# RM2025___IMCA.net
KiCad netlist of a schematic drawn in EasyEDA Pro
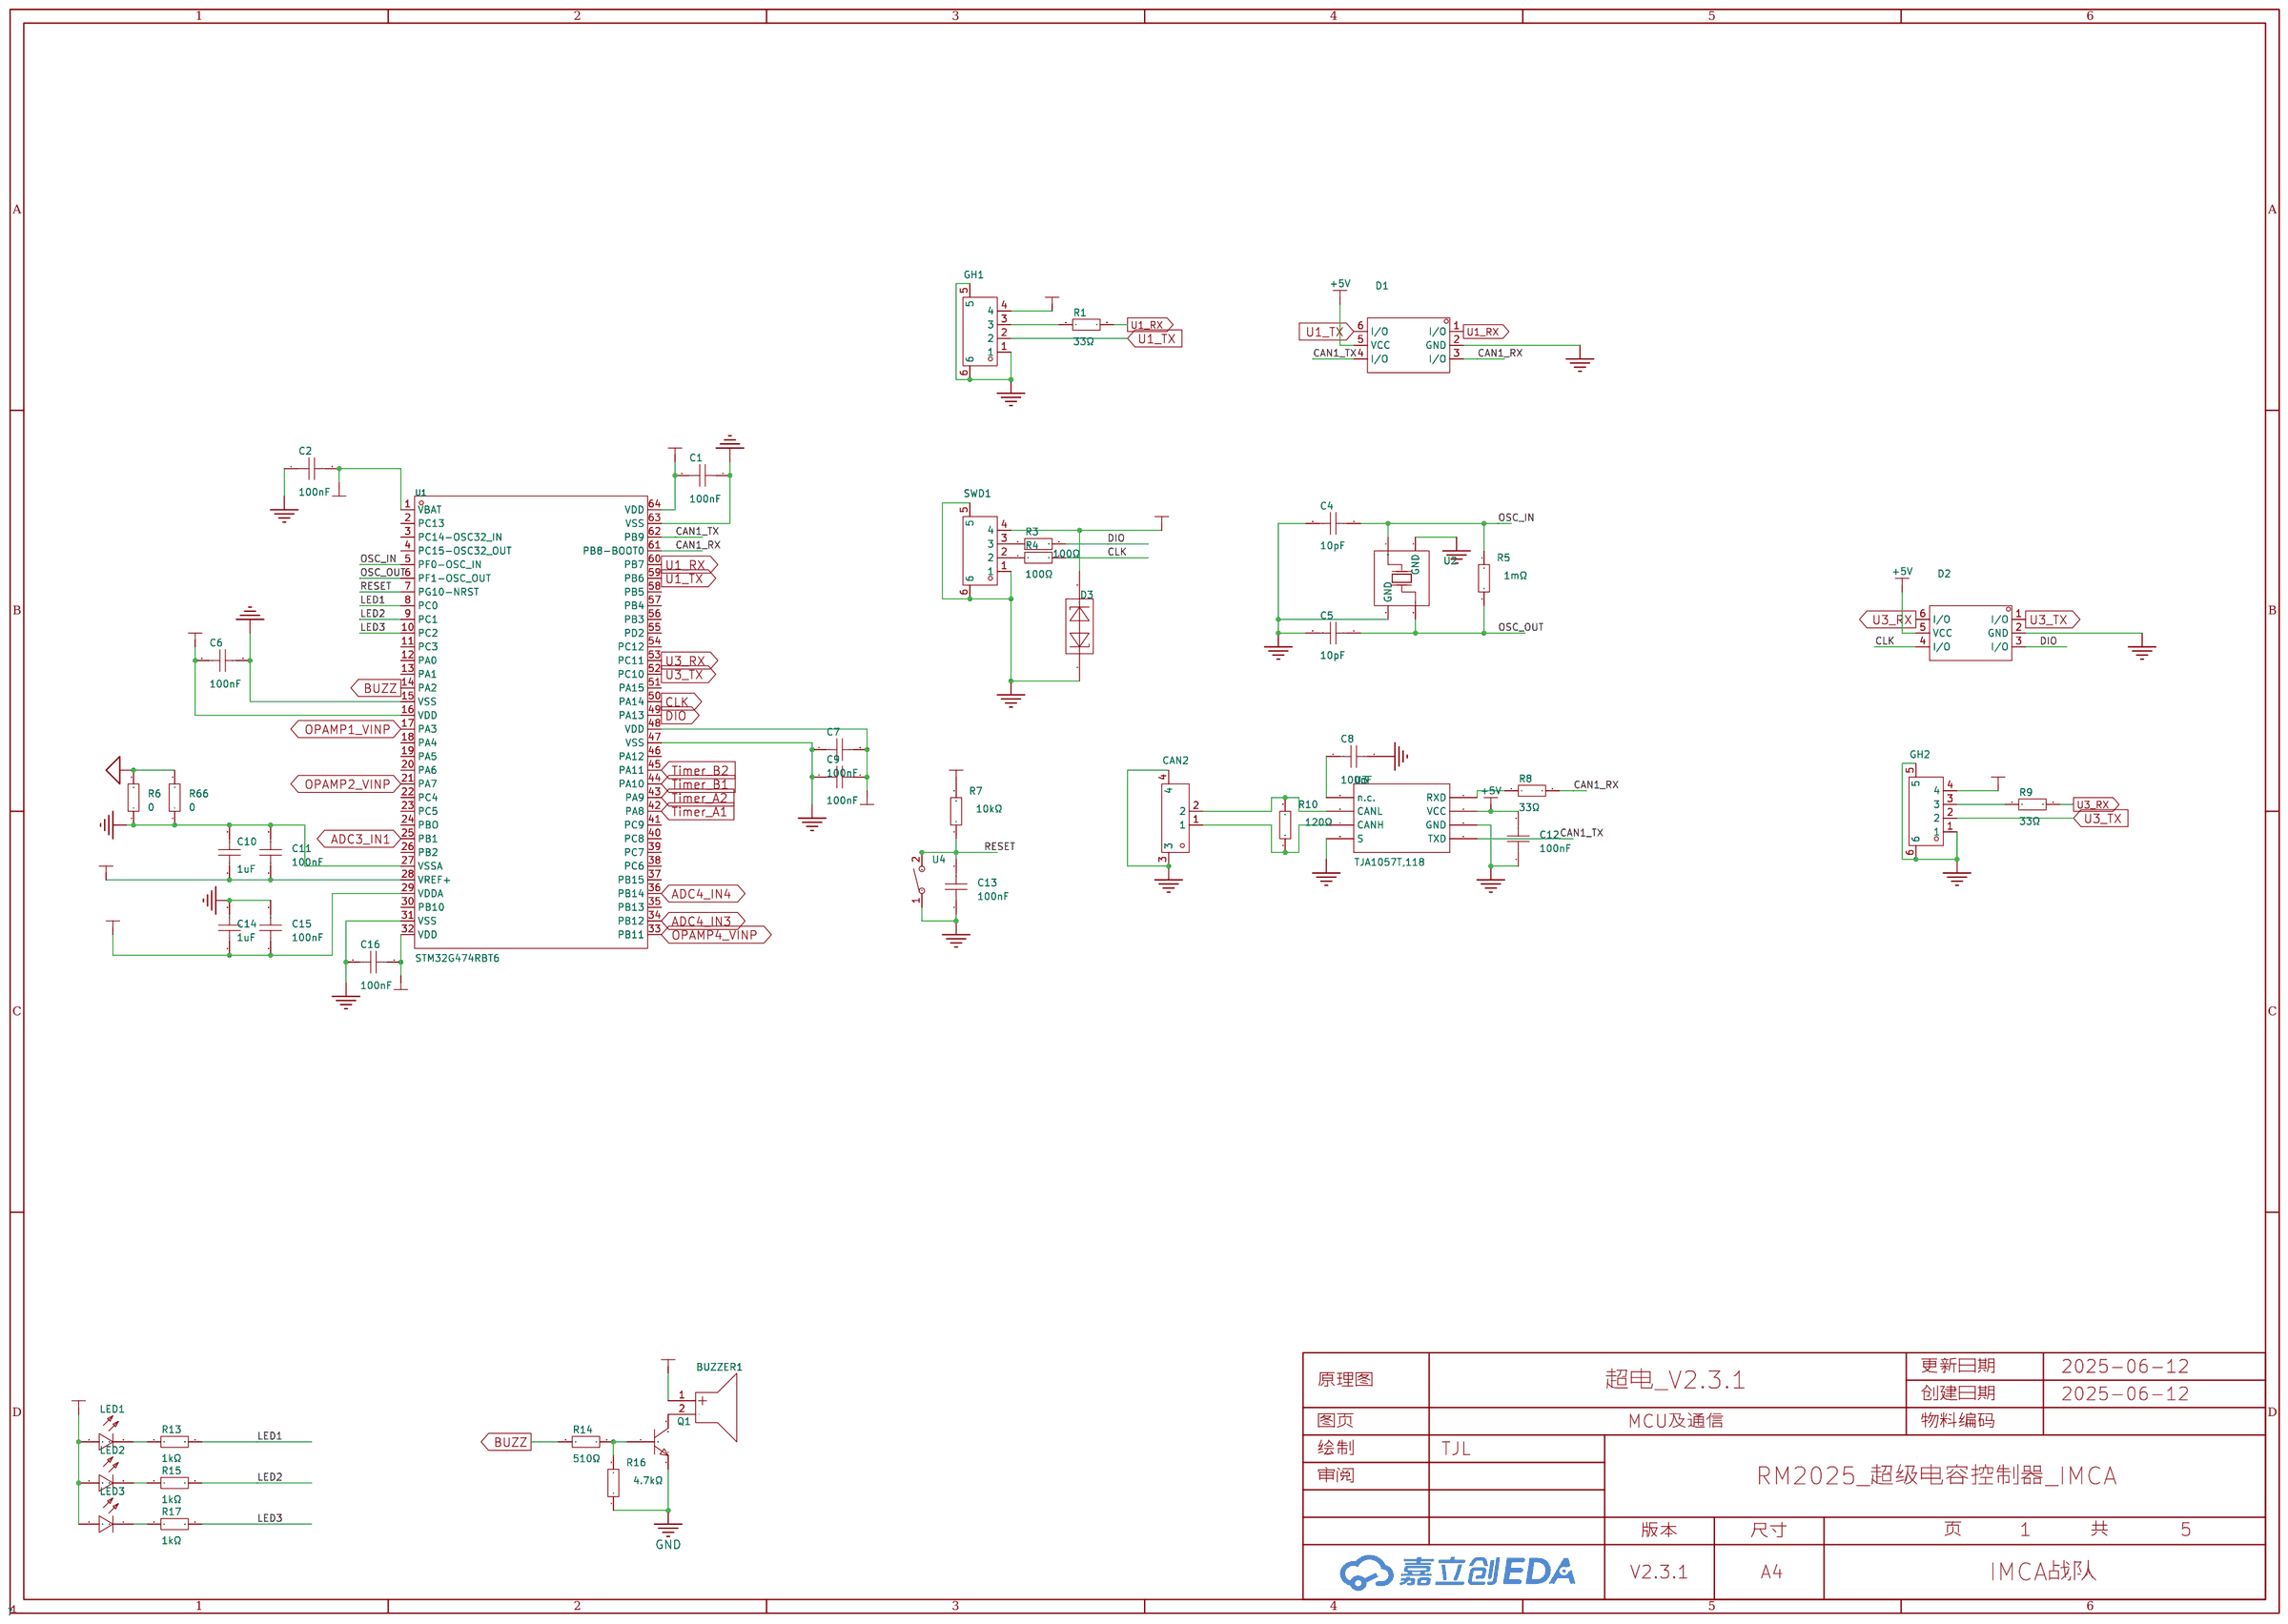
[diagram p0: MCU及通信]
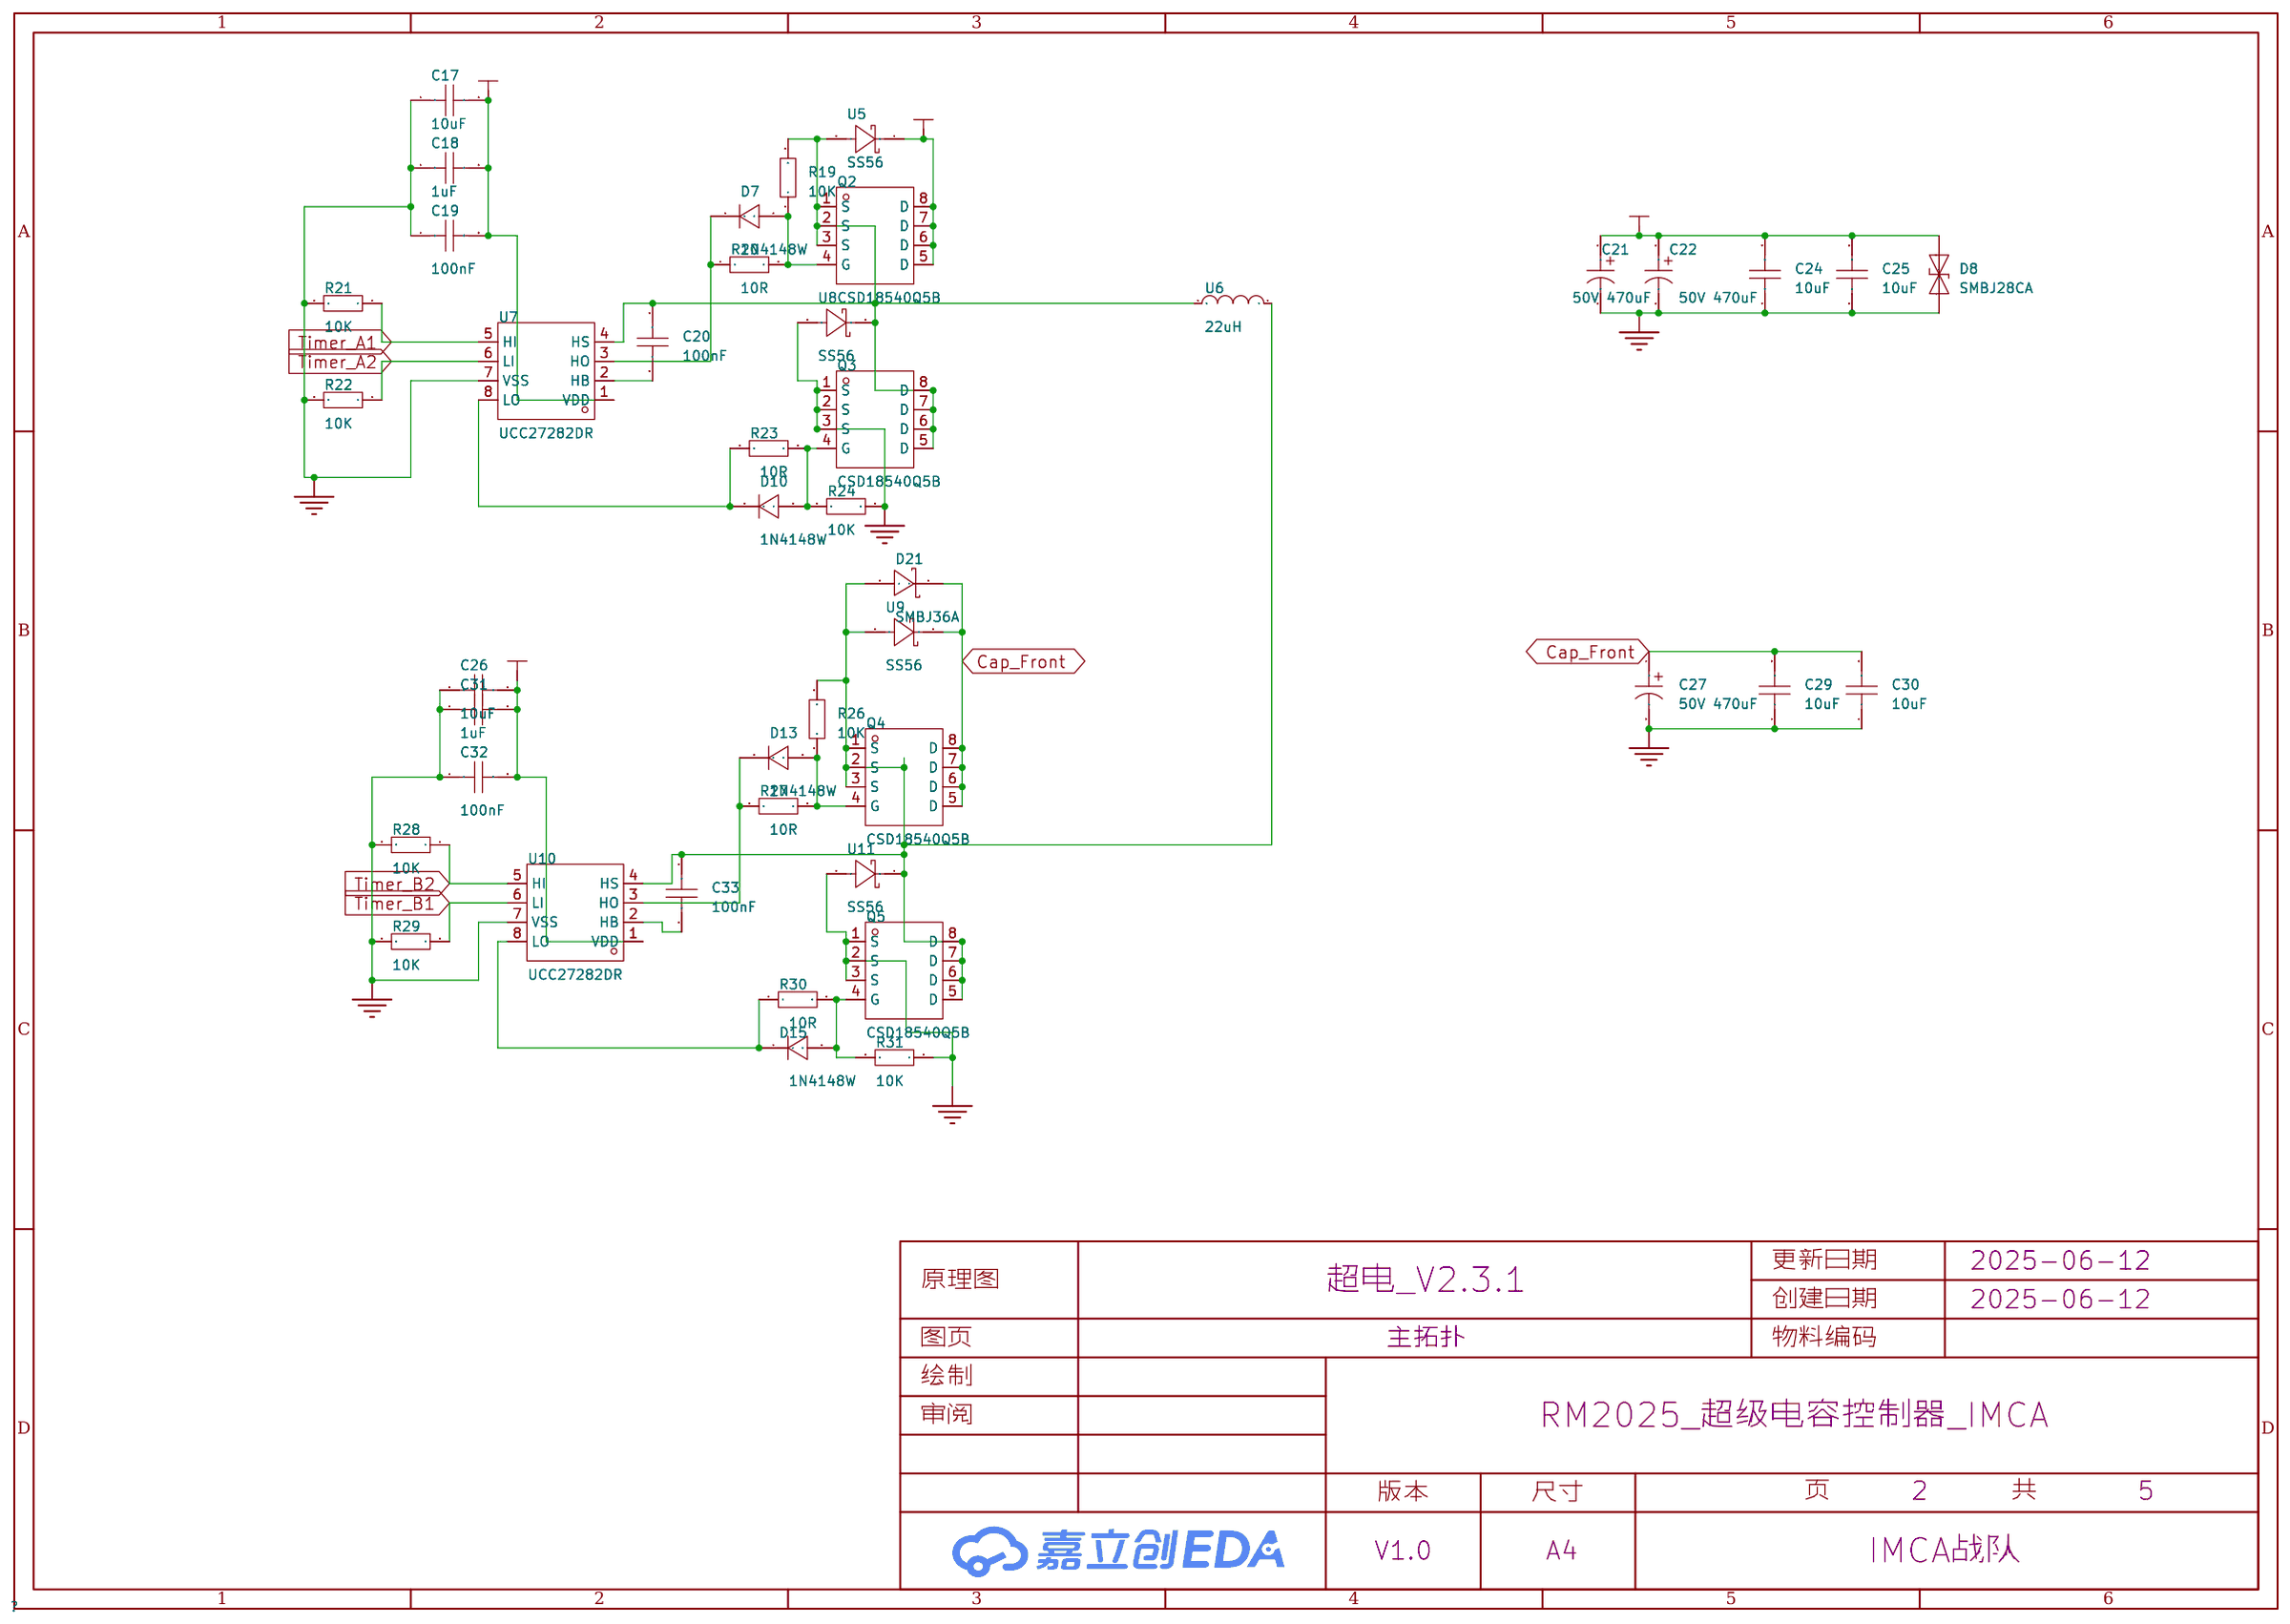
[diagram p1: 主拓扑]
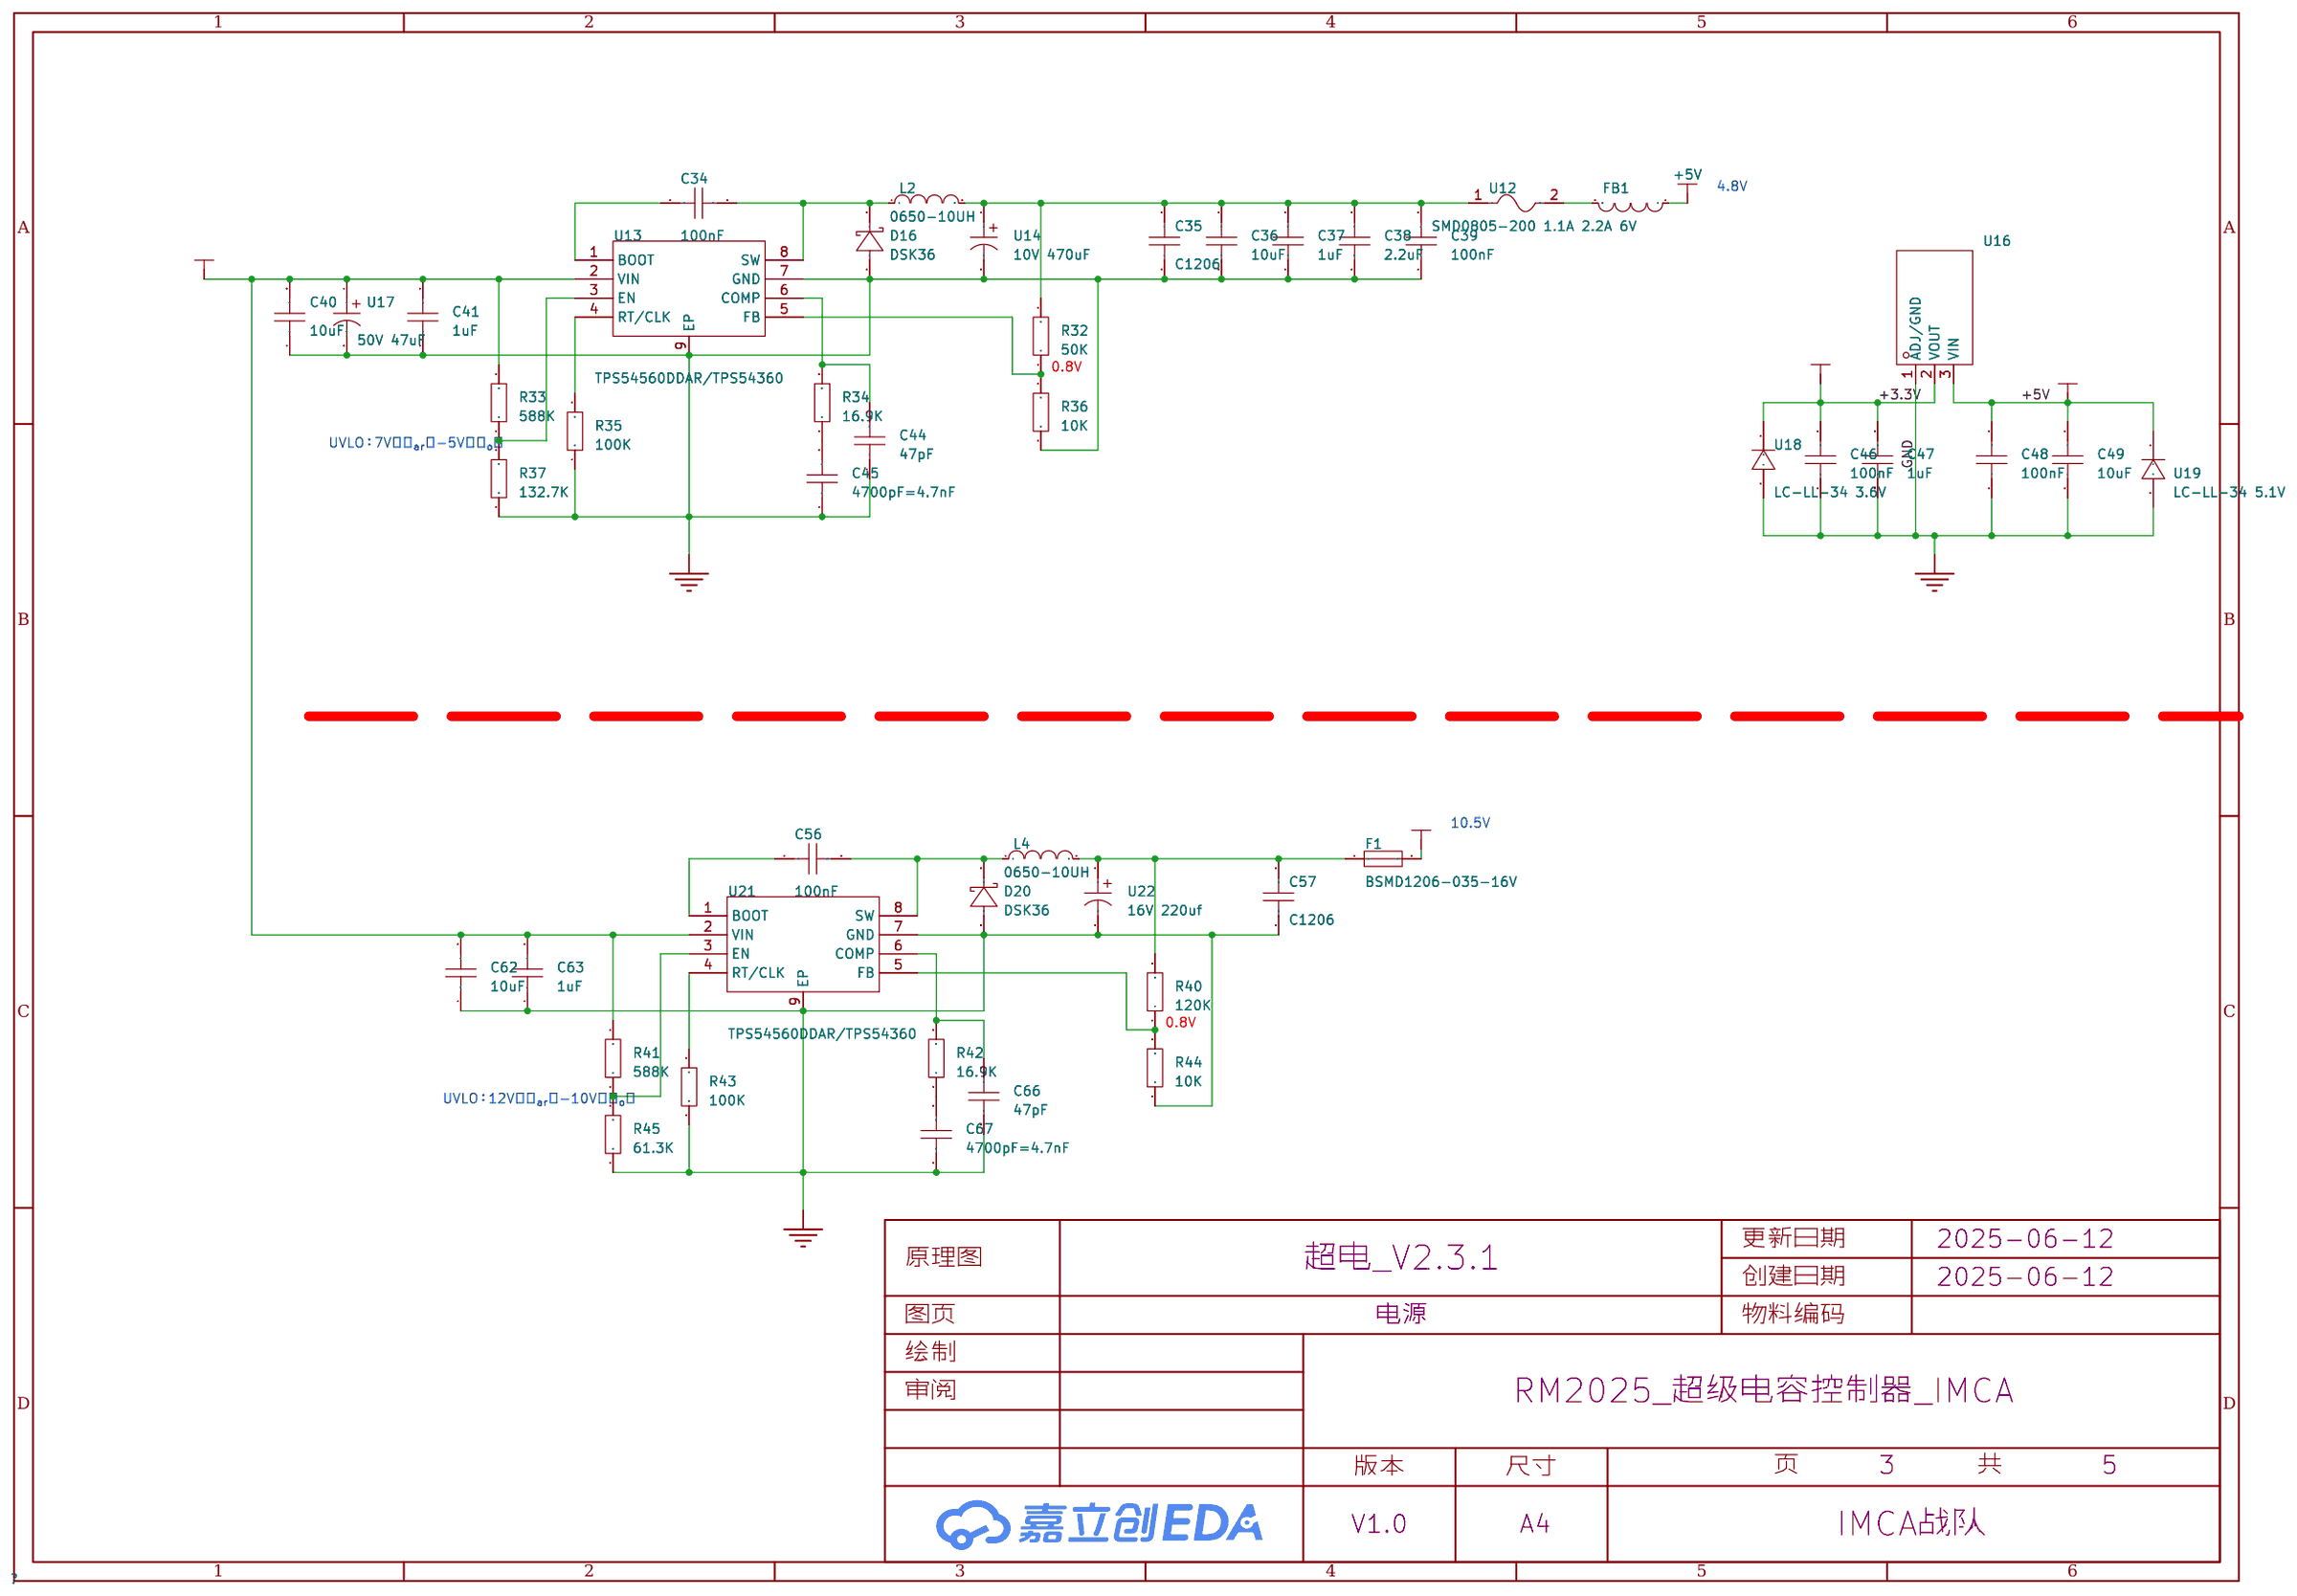
[diagram p2: 电源]
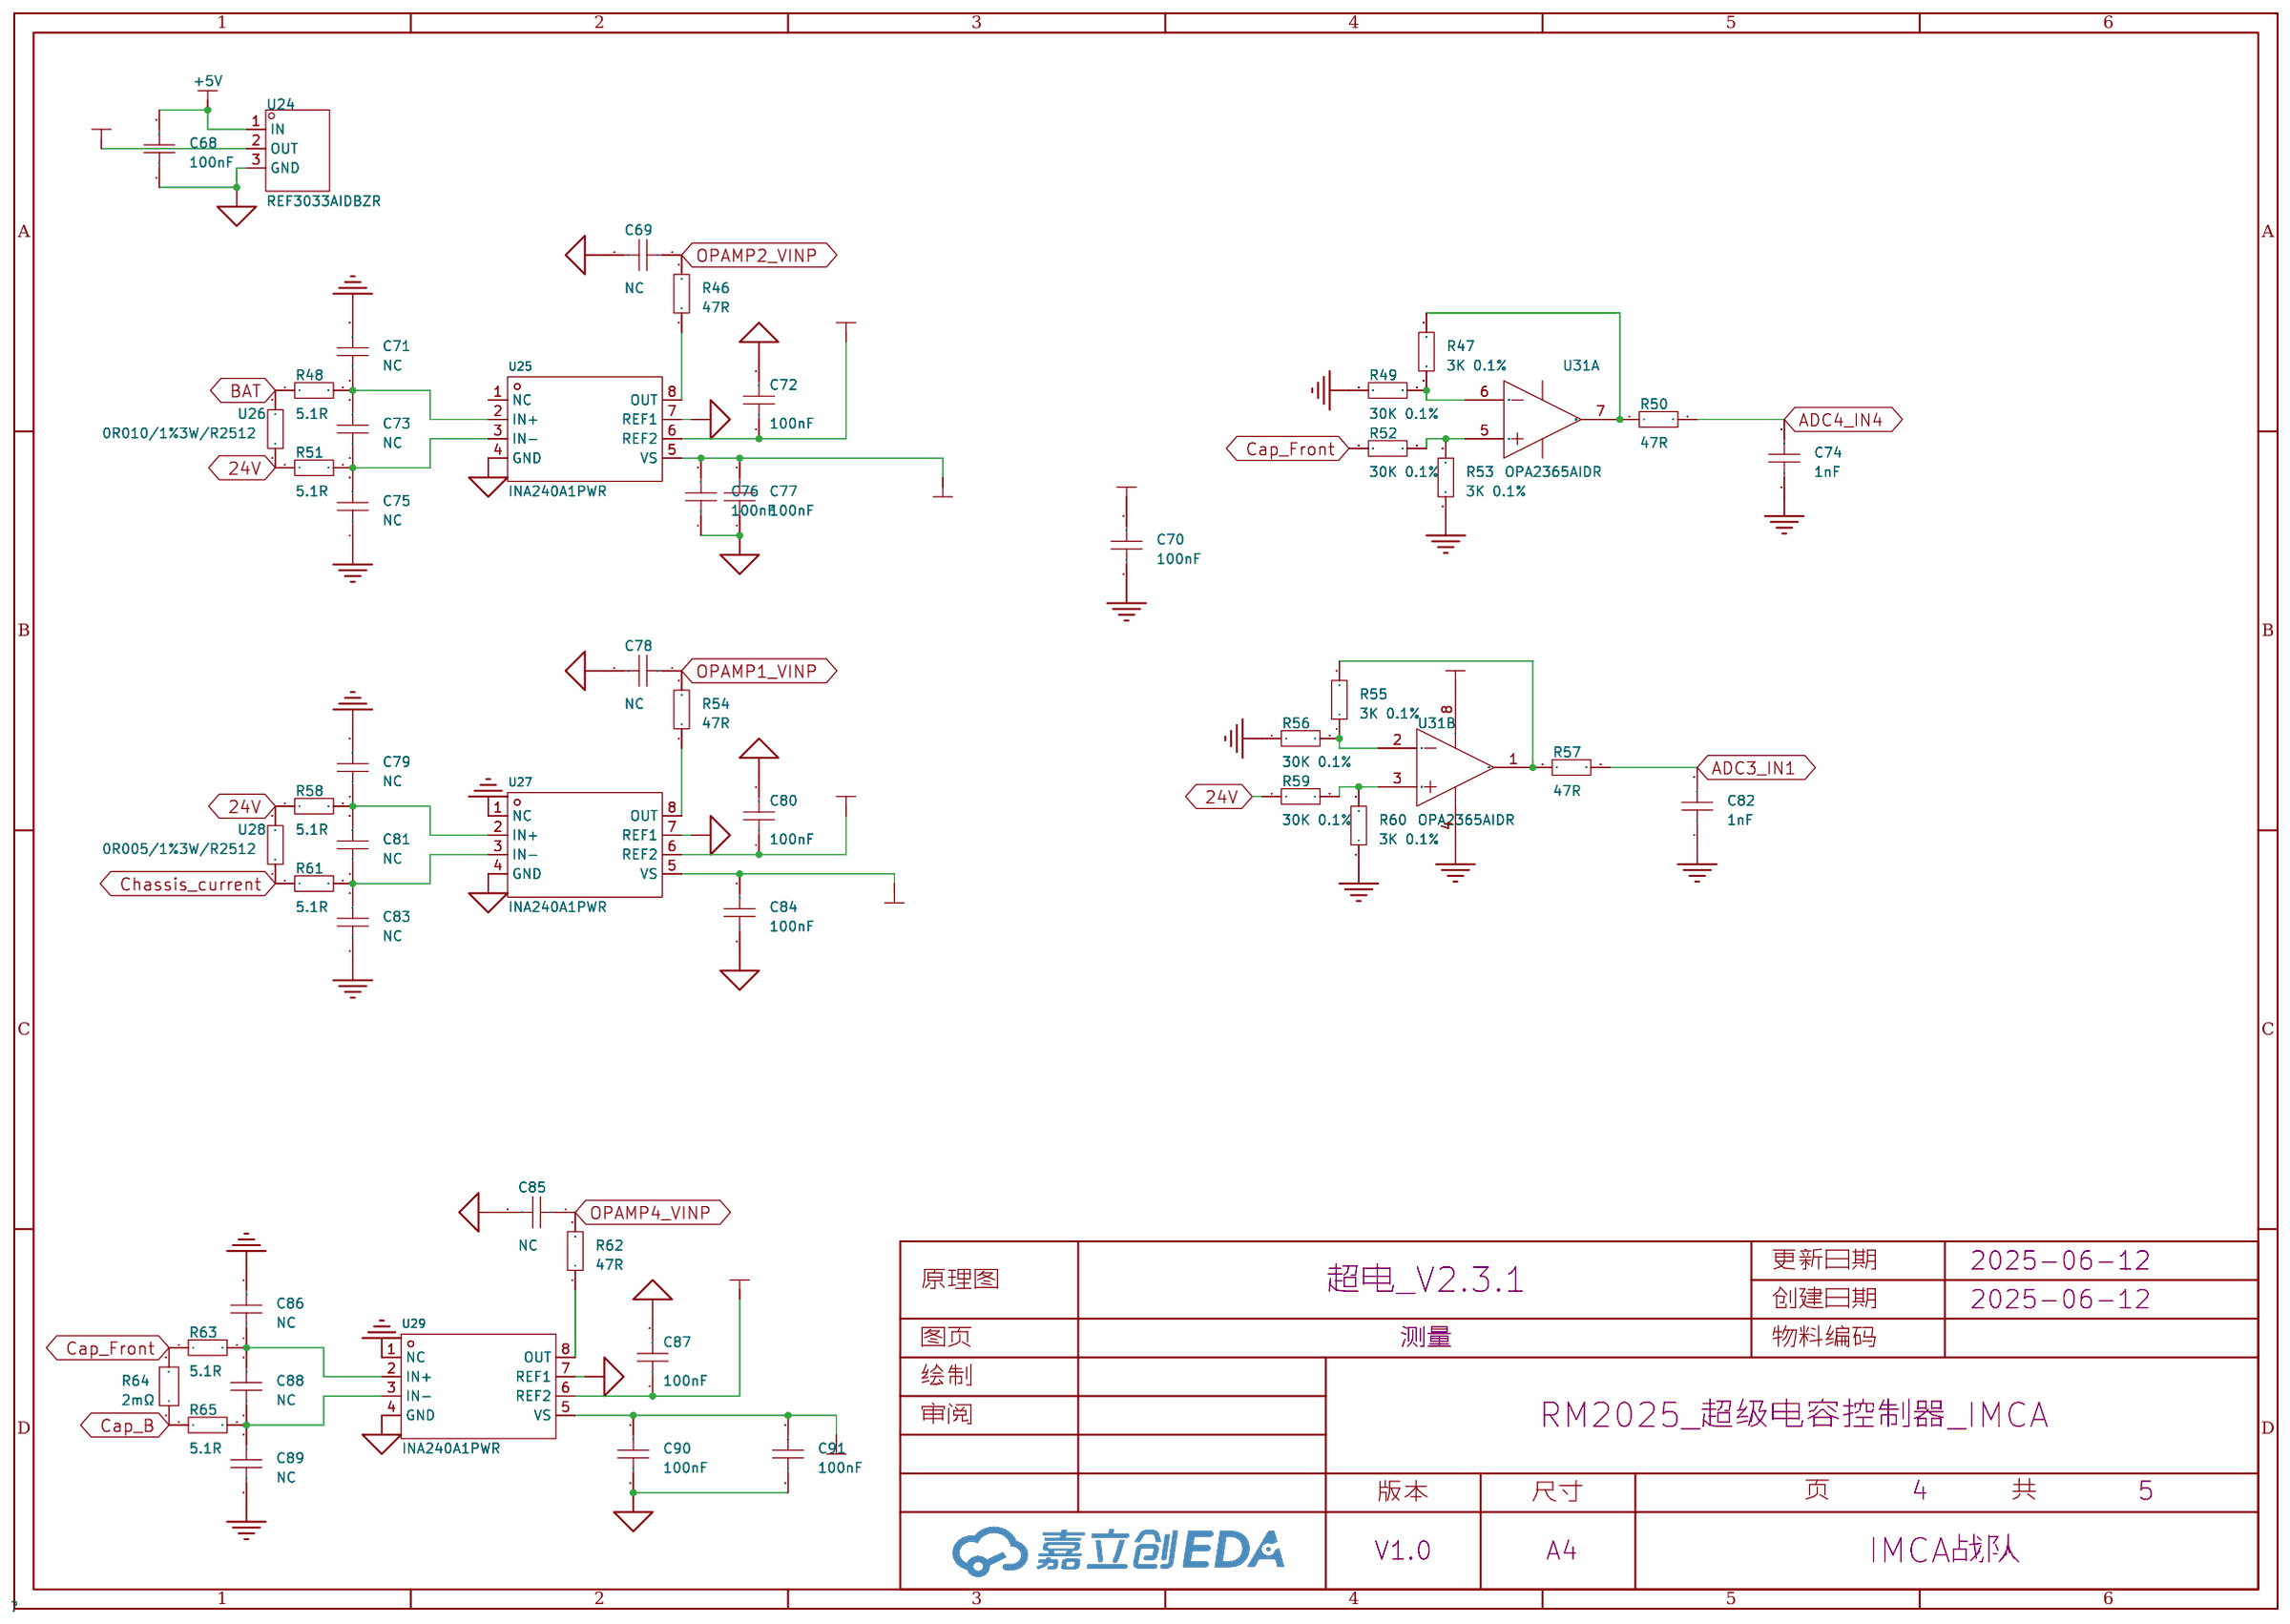
[diagram p3: 测量]
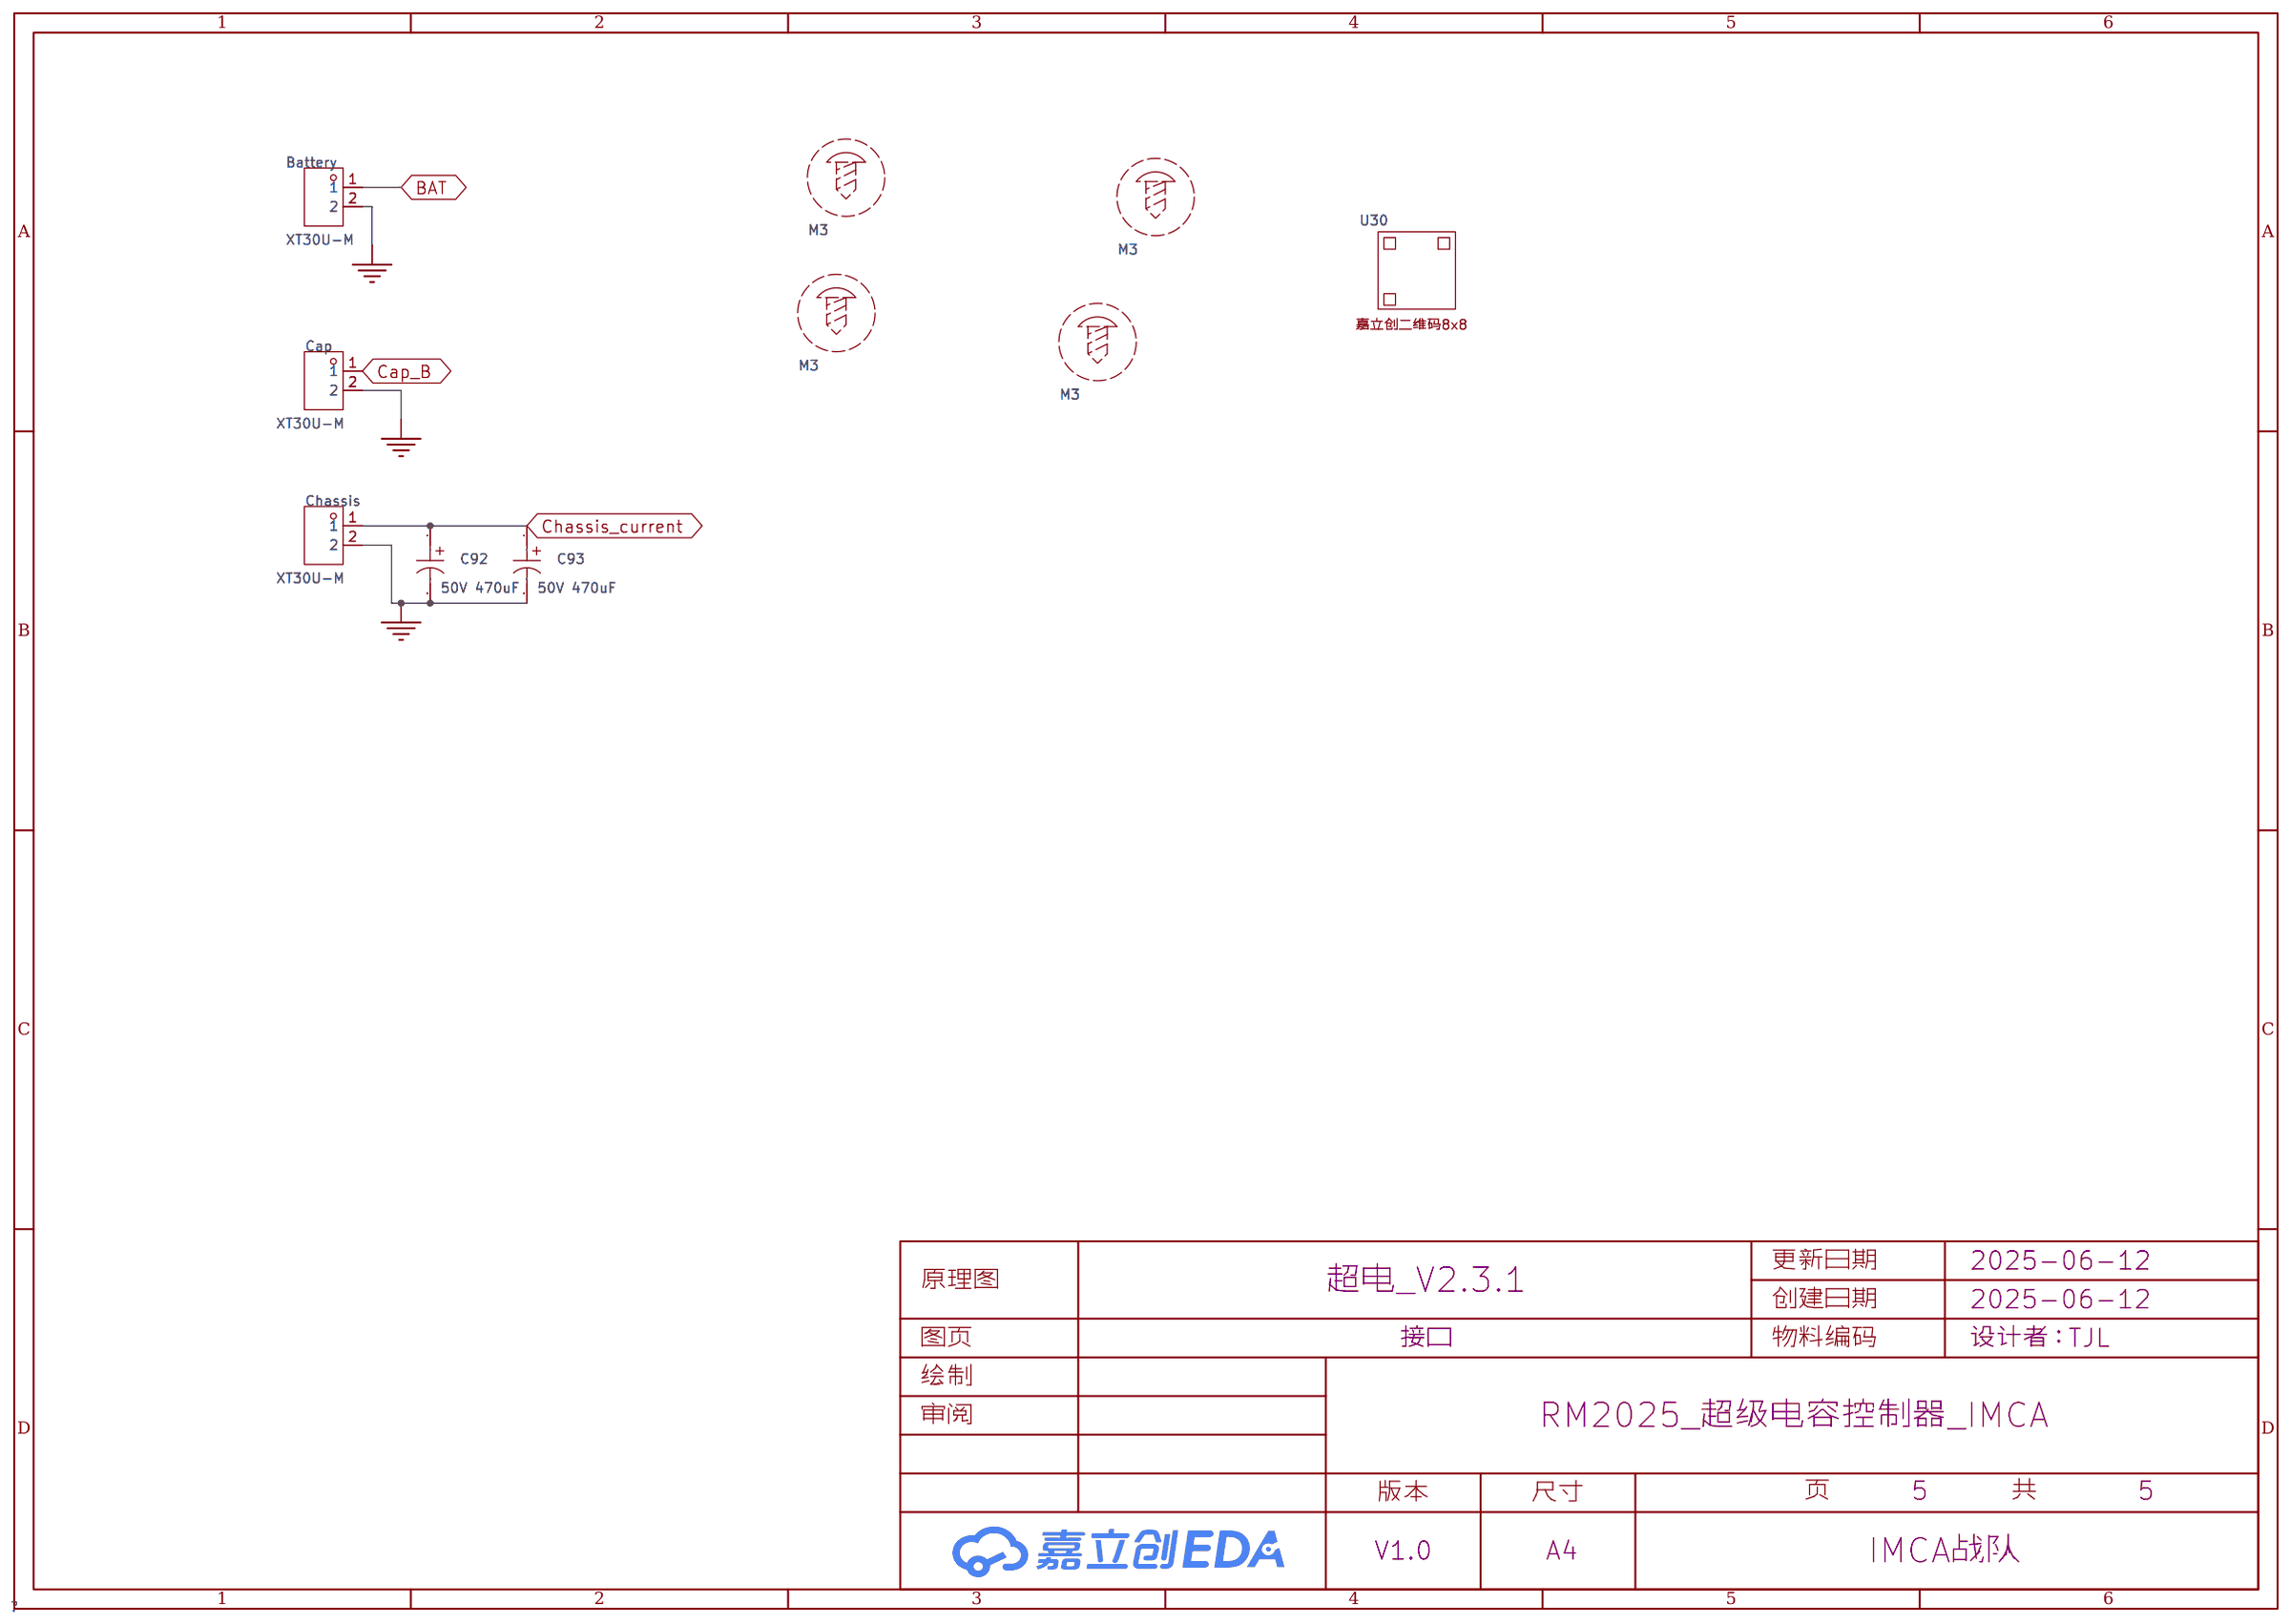
[diagram p4: 接口]

(export (version "E")
  (design (tool "Eeschema 10.0.6"))
  (components
    (comp (ref "BUZZER1")
      (value "~")
      (footprint "easyedapro:BUZ-TH_BD9.0-P5.00-D0.6-L-FD")
      (fields (field (name "Manufacturer Part") "有源蜂鸣器直径9*5.5mm3V"))
      (libsource (lib "easyedapro") (part "有源蜂鸣器直径9*5.5MM3V"))
    )
    (comp (ref "C1")
      (value "100nF")
      (footprint "easyedapro:C1206")
      (libsource (lib "easyedapro") (part "CapAcitance"))
    )
    (comp (ref "C2")
      (value "100nF")
      (footprint "easyedapro:C1206")
      (libsource (lib "easyedapro") (part "CapAcitance"))
    )
    (comp (ref "C4")
      (value "10pF")
      (footprint "easyedapro:C0603")
      (description "容值:100nF;精度:±10%;额定电压:50V;温度系数:X7R;")
      (fields
        (field (name "Manufacturer Part") "CC0603KRX7R9BB104")
        (field (name "Manufacturer") "YAGEO(国巨)")
      )
      (libsource (lib "easyedapro") (part "CC0603KRX7R9BB104"))
    )
    (comp (ref "C5")
      (value "10pF")
      (footprint "easyedapro:C0603")
      (description "容值:100nF;精度:±10%;额定电压:50V;温度系数:X7R;")
      (fields
        (field (name "Manufacturer Part") "CC0603KRX7R9BB104")
        (field (name "Manufacturer") "YAGEO(国巨)")
      )
      (libsource (lib "easyedapro") (part "CC0603KRX7R9BB104"))
    )
    (comp (ref "C6")
      (value "100nF")
      (footprint "easyedapro:C1206")
      (libsource (lib "easyedapro") (part "CapAcitance"))
    )
    (comp (ref "C7")
      (value "100nF")
      (footprint "easyedapro:C1206")
      (libsource (lib "easyedapro") (part "CapAcitance"))
    )
    (comp (ref "C8")
      (value "100nF")
      (footprint "easyedapro:C1206")
      (libsource (lib "easyedapro") (part "CapAcitance"))
    )
    (comp (ref "C9")
      (value "100nF")
      (footprint "easyedapro:C1206")
      (libsource (lib "easyedapro") (part "CapAcitance"))
    )
    (comp (ref "C10")
      (value "1uF")
      (footprint "easyedapro:C1206")
      (libsource (lib "easyedapro") (part "CapAcitance"))
    )
    (comp (ref "C11")
      (value "100nF")
      (footprint "easyedapro:C1206")
      (libsource (lib "easyedapro") (part "CapAcitance"))
    )
    (comp (ref "C12")
      (value "100nF")
      (footprint "easyedapro:C1206")
      (libsource (lib "easyedapro") (part "CapAcitance"))
    )
    (comp (ref "C13")
      (value "100nF")
      (footprint "easyedapro:C1206")
      (libsource (lib "easyedapro") (part "CapAcitance"))
    )
    (comp (ref "C14")
      (value "1uF")
      (footprint "easyedapro:C1206")
      (libsource (lib "easyedapro") (part "CapAcitance"))
    )
    (comp (ref "C15")
      (value "100nF")
      (footprint "easyedapro:C1206")
      (libsource (lib "easyedapro") (part "CapAcitance"))
    )
    (comp (ref "C16")
      (value "100nF")
      (footprint "easyedapro:C1206")
      (libsource (lib "easyedapro") (part "CapAcitance"))
    )
    (comp (ref "CAN2")
      (value "~")
      (footprint "easyedapro:CONN-SMD_2P-P1.25_GH1.25-2P")
      (fields
        (field (name "Manufacturer Part") "GH1.25-2PLTPZ")
        (field (name "Manufacturer") "BOOMELE(博穆精密)")
      )
      (libsource (lib "easyedapro") (part "GH1.25-2PLTPZ"))
    )
    (comp (ref "D1")
      (value "SRV05-4HTG-D")
      (footprint "easyedapro:SOT-23-6_L2.9-W1.6-P0.95-LS2.8-BR")
      (fields
        (field (name "Manufacturer Part") "BST236A054U")
        (field (name "Manufacturer") "Bourne Semicon (Shenzhen)")
      )
      (libsource (lib "easyedapro") (part "BST236A054U"))
    )
    (comp (ref "D2")
      (value "SRV05-4HTG-D")
      (footprint "easyedapro:SOT-23-6_L2.9-W1.6-P0.95-LS2.8-BR")
      (fields
        (field (name "Manufacturer Part") "BST236A054U")
        (field (name "Manufacturer") "Bourne Semicon (Shenzhen)")
      )
      (libsource (lib "easyedapro") (part "BST236A054U"))
    )
    (comp (ref "D3")
      (value "~")
      (footprint "easyedapro:SOD-323_L1.8-W1.3-LS2.5-BI")
      (description "极性:Bidirectional;反向关断电压（典型值）:5V;击穿电压（最小值）:7V;箝位电压:33V;峰值脉冲电流（10/1000us）:15A;")
      (fields
        (field (name "Manufacturer Part") "PESD5V0L1BA,115")
        (field (name "Manufacturer") "Nexperia(安世)")
      )
      (libsource (lib "easyedapro") (part "PESD5V0L1BA,115"))
    )
    (comp (ref "GH1")
      (value "U1")
      (footprint "easyedapro:CONN-SMD_4P-P2.00_GH1.25-WS-4P")
      (fields (field (name "Manufacturer Part") "GH1.25-WS-4P"))
      (libsource (lib "easyedapro") (part "GH1.25-WS-4P"))
    )
    (comp (ref "GH2")
      (value "U3")
      (footprint "easyedapro:CONN-SMD_4P-P2.00_GH1.25-WS-4P")
      (fields (field (name "Manufacturer Part") "GH1.25-WS-4P"))
      (libsource (lib "easyedapro") (part "GH1.25-WS-4P"))
    )
    (comp (ref "LED1")
      (value "~")
      (footprint "easyedapro:LED0603-R-RD")
      (description "照明颜色:翠绿;色温 - CCT（K）:-;主波长/色坐标:520~535nm;")
      (fields
        (field (name "Manufacturer Part") "19-217/GHC-YR1S2/3T")
        (field (name "Manufacturer") "EVERLIGHT(台湾亿光)")
      )
      (libsource (lib "easyedapro") (part "19-217/GHC-YR1S2/3T"))
    )
    (comp (ref "LED2")
      (value "~")
      (footprint "easyedapro:LED0603-R-RD")
      (description "照明颜色:翠绿;色温 - CCT（K）:-;主波长/色坐标:520~535nm;")
      (fields
        (field (name "Manufacturer Part") "19-217/GHC-YR1S2/3T")
        (field (name "Manufacturer") "EVERLIGHT(台湾亿光)")
      )
      (libsource (lib "easyedapro") (part "19-217/GHC-YR1S2/3T"))
    )
    (comp (ref "LED3")
      (value "~")
      (footprint "easyedapro:LED0603-R-RD")
      (description "照明颜色:翠绿;色温 - CCT（K）:-;主波长/色坐标:520~535nm;")
      (fields
        (field (name "Manufacturer Part") "19-217/GHC-YR1S2/3T")
        (field (name "Manufacturer") "EVERLIGHT(台湾亿光)")
      )
      (libsource (lib "easyedapro") (part "19-217/GHC-YR1S2/3T"))
    )
    (comp (ref "Q1")
      (value "~")
      (footprint "easyedapro:SOT-23-3_L2.9-W1.3-P1.90-LS2.4-BR")
      (description "额定功率:300mW;集电极电流Ic:1.5A;集射极击穿电压Vce:25V;晶体管类型:NPN;")
      (fields (field (name "Manufacturer Part") "SS8050"))
      (libsource (lib "easyedapro") (part "SS8050_C139513"))
    )
    (comp (ref "R1")
      (value "33Ω")
      (footprint "easyedapro:R0603")
      (description "电阻类型:薄膜电阻;阻值:10kΩ;精度:±0.1%;功率:100mW;温度系数:±25ppm/;最大工作电压:75V;工作温度范围:-55~+155;")
      (fields
        (field (name "Manufacturer Part") "TR0603B10K0P0525Z")
        (field (name "Manufacturer") "EVER OHMS(天二科技)")
      )
      (libsource (lib "easyedapro") (part "TR0603B10KP05250.1W"))
    )
    (comp (ref "R3")
      (value "100Ω")
      (footprint "easyedapro:R0603")
      (description "电阻类型:薄膜电阻;阻值:10kΩ;精度:±0.1%;功率:100mW;温度系数:±25ppm/;最大工作电压:75V;工作温度范围:-55~+155;")
      (fields
        (field (name "Manufacturer Part") "TR0603B10K0P0525Z")
        (field (name "Manufacturer") "EVER OHMS(天二科技)")
      )
      (libsource (lib "easyedapro") (part "TR0603B10KP05250.1W"))
    )
    (comp (ref "R4")
      (value "100Ω")
      (footprint "easyedapro:R0603")
      (description "电阻类型:薄膜电阻;阻值:10kΩ;精度:±0.1%;功率:100mW;温度系数:±25ppm/;最大工作电压:75V;工作温度范围:-55~+155;")
      (fields
        (field (name "Manufacturer Part") "TR0603B10K0P0525Z")
        (field (name "Manufacturer") "EVER OHMS(天二科技)")
      )
      (libsource (lib "easyedapro") (part "TR0603B10KP05250.1W"))
    )
    (comp (ref "R5")
      (value "1mΩ")
      (footprint "easyedapro:R0603")
      (description "电阻类型:薄膜电阻;阻值:10kΩ;精度:±0.1%;功率:100mW;温度系数:±25ppm/;最大工作电压:75V;工作温度范围:-55~+155;")
      (fields
        (field (name "Manufacturer Part") "TR0603B10K0P0525Z")
        (field (name "Manufacturer") "EVER OHMS(天二科技)")
      )
      (libsource (lib "easyedapro") (part "TR0603B10KP05250.1W"))
    )
    (comp (ref "R6") (value "0") (footprint "easyedapro:R0603") (libsource (lib "easyedapro") (part "电阻")))
    (comp (ref "R7")
      (value "10kΩ")
      (footprint "easyedapro:R0603")
      (description "电阻类型:薄膜电阻;阻值:10kΩ;精度:±0.1%;功率:100mW;温度系数:±25ppm/;最大工作电压:75V;工作温度范围:-55~+155;")
      (fields
        (field (name "Manufacturer Part") "TR0603B10K0P0525Z")
        (field (name "Manufacturer") "EVER OHMS(天二科技)")
      )
      (libsource (lib "easyedapro") (part "TR0603B10KP05250.1W"))
    )
    (comp (ref "R8")
      (value "33Ω")
      (footprint "easyedapro:R0603")
      (description "电阻类型:薄膜电阻;阻值:10kΩ;精度:±0.1%;功率:100mW;温度系数:±25ppm/;最大工作电压:75V;工作温度范围:-55~+155;")
      (fields
        (field (name "Manufacturer Part") "TR0603B10K0P0525Z")
        (field (name "Manufacturer") "EVER OHMS(天二科技)")
      )
      (libsource (lib "easyedapro") (part "TR0603B10KP05250.1W"))
    )
    (comp (ref "R9")
      (value "33Ω")
      (footprint "easyedapro:R0603")
      (description "电阻类型:薄膜电阻;阻值:10kΩ;精度:±0.1%;功率:100mW;温度系数:±25ppm/;最大工作电压:75V;工作温度范围:-55~+155;")
      (fields
        (field (name "Manufacturer Part") "TR0603B10K0P0525Z")
        (field (name "Manufacturer") "EVER OHMS(天二科技)")
      )
      (libsource (lib "easyedapro") (part "TR0603B10KP05250.1W"))
    )
    (comp (ref "R10")
      (value "120Ω")
      (footprint "easyedapro:R0603")
      (description "电阻类型:薄膜电阻;阻值:10kΩ;精度:±0.1%;功率:100mW;温度系数:±25ppm/;最大工作电压:75V;工作温度范围:-55~+155;")
      (fields
        (field (name "Manufacturer Part") "TR0603B10K0P0525Z")
        (field (name "Manufacturer") "EVER OHMS(天二科技)")
      )
      (libsource (lib "easyedapro") (part "R_0603_EU"))
    )
    (comp (ref "R13")
      (value "1kΩ")
      (footprint "easyedapro:R0603")
      (description "电阻类型:薄膜电阻;阻值:10kΩ;精度:±0.1%;功率:100mW;温度系数:±25ppm/;最大工作电压:75V;工作温度范围:-55~+155;")
      (fields
        (field (name "Manufacturer Part") "TR0603B10K0P0525Z")
        (field (name "Manufacturer") "EVER OHMS(天二科技)")
      )
      (libsource (lib "easyedapro") (part "TR0603B10KP05250.1W"))
    )
    (comp (ref "R14")
      (value "510Ω")
      (footprint "easyedapro:R0603")
      (description "电阻类型:薄膜电阻;阻值:10kΩ;精度:±0.1%;功率:100mW;温度系数:±25ppm/;最大工作电压:75V;工作温度范围:-55~+155;")
      (fields
        (field (name "Manufacturer Part") "TR0603B10K0P0525Z")
        (field (name "Manufacturer") "EVER OHMS(天二科技)")
      )
      (libsource (lib "easyedapro") (part "R_0603_EU"))
    )
    (comp (ref "R15")
      (value "1kΩ")
      (footprint "easyedapro:R0603")
      (description "电阻类型:薄膜电阻;阻值:10kΩ;精度:±0.1%;功率:100mW;温度系数:±25ppm/;最大工作电压:75V;工作温度范围:-55~+155;")
      (fields
        (field (name "Manufacturer Part") "TR0603B10K0P0525Z")
        (field (name "Manufacturer") "EVER OHMS(天二科技)")
      )
      (libsource (lib "easyedapro") (part "TR0603B10KP05250.1W"))
    )
    (comp (ref "R16")
      (value "4.7kΩ")
      (footprint "easyedapro:R0603")
      (description "电阻类型:薄膜电阻;阻值:10kΩ;精度:±0.1%;功率:100mW;温度系数:±25ppm/;最大工作电压:75V;工作温度范围:-55~+155;")
      (fields
        (field (name "Manufacturer Part") "TR0603B10K0P0525Z")
        (field (name "Manufacturer") "EVER OHMS(天二科技)")
      )
      (libsource (lib "easyedapro") (part "R_0603_EU"))
    )
    (comp (ref "R17")
      (value "1kΩ")
      (footprint "easyedapro:R0603")
      (description "电阻类型:薄膜电阻;阻值:10kΩ;精度:±0.1%;功率:100mW;温度系数:±25ppm/;最大工作电压:75V;工作温度范围:-55~+155;")
      (fields
        (field (name "Manufacturer Part") "TR0603B10K0P0525Z")
        (field (name "Manufacturer") "EVER OHMS(天二科技)")
      )
      (libsource (lib "easyedapro") (part "TR0603B10KP05250.1W"))
    )
    (comp (ref "R66") (value "0") (footprint "easyedapro:R0603") (libsource (lib "easyedapro") (part "电阻")))
    (comp (ref "SWD1")
      (value "~")
      (footprint "easyedapro:CONN-SMD_4P-P2.00_GH1.25-WS-4P")
      (fields (field (name "Manufacturer Part") "GH1.25-WS-4P"))
      (libsource (lib "easyedapro") (part "GH1.25-WS-4P"))
    )
    (comp (ref "U1")
      (value "STM32G474RBT6")
      (footprint "easyedapro:LQFP-64_L10.0-W10.0-P0.50-LS12.0-BL")
      (description "CPU内核:CM4;程序存储容量:128KB;RAM总容量:128KB;GPIO端口数量:52;工作电压范围:1.71V~3.6V;CPU最大主频:170MHz;程序存储器类型:FLASH;")
      (fields (field (name "Manufacturer") "ST(意法半导体)"))
      (libsource (lib "easyedapro") (part "STM32G474RBT6"))
    )
    (comp (ref "U2")
      (value "~")
      (footprint "easyedapro:CRYSTAL-SMD_4P-L3.2-W2.5-BL-2")
      (fields (field (name "Manufacturer Part") "SMDOSCC25X32X11"))
      (libsource (lib "easyedapro") (part "SMDOSCC25X32X11"))
    )
    (comp (ref "U3")
      (value "TJA1057T,118")
      (footprint "easyedapro:SOIC-8_L4.9-W3.9-P1.27-LS6.0-BL")
      (description "类型:收发器;数据速率:5Mbps;")
      (fields (field (name "Manufacturer") "NXP(恩智浦)"))
      (libsource (lib "easyedapro") (part "TJA1057T,118"))
    )
    (comp (ref "U4")
      (value "~")
      (footprint "easyedapro:SW-SMD_L4.0-W3.0-LS4.8-1")
      (fields (field (name "Manufacturer Part") "3*4 龟仔/微动/轻触开关"))
      (libsource (lib "easyedapro") (part "3*4 龟仔/微动/轻触开关"))
    )
    (comp (ref "C17")
      (value "10uF")
      (footprint "easyedapro:C1206")
      (libsource (lib "easyedapro") (part "CapAcitance"))
    )
    (comp (ref "C18")
      (value "1uF")
      (footprint "easyedapro:C1206")
      (libsource (lib "easyedapro") (part "CapAcitance"))
    )
    (comp (ref "C19")
      (value "100nF")
      (footprint "easyedapro:C1206")
      (libsource (lib "easyedapro") (part "CapAcitance"))
    )
    (comp (ref "C20")
      (value "100nF")
      (footprint "easyedapro:C1206")
      (libsource (lib "easyedapro") (part "CapAcitance"))
    )
    (comp (ref "C21")
      (value "50V 470uF")
      (footprint "easyedapro:CAP-TH_BD10.0-P5.00-D0.6-FD-A")
      (fields
        (field (name "Manufacturer Part") "160AREP222M10B0L05T")
        (field (name "Manufacturer") "APAQ(钰邦)")
      )
      (libsource (lib "easyedapro") (part "160AREP222M10B0L05T"))
    )
    (comp (ref "C22")
      (value "50V 470uF")
      (footprint "easyedapro:CAP-TH_BD10.0-P5.00-D0.6-FD-A")
      (fields
        (field (name "Manufacturer Part") "160AREP222M10B0L05T")
        (field (name "Manufacturer") "APAQ(钰邦)")
      )
      (libsource (lib "easyedapro") (part "160AREP222M10B0L05T"))
    )
    (comp (ref "C24")
      (value "10uF")
      (footprint "easyedapro:C1206")
      (libsource (lib "easyedapro") (part "CapAcitance"))
    )
    (comp (ref "C25")
      (value "10uF")
      (footprint "easyedapro:C1206")
      (libsource (lib "easyedapro") (part "CapAcitance"))
    )
    (comp (ref "C26")
      (value "10uF")
      (footprint "easyedapro:C1206")
      (libsource (lib "easyedapro") (part "CapAcitance"))
    )
    (comp (ref "C27")
      (value "50V 470uF")
      (footprint "easyedapro:CAP-TH_BD10.0-P5.00-D0.6-FD-A")
      (fields
        (field (name "Manufacturer Part") "160AREP222M10B0L05T")
        (field (name "Manufacturer") "APAQ(钰邦)")
      )
      (libsource (lib "easyedapro") (part "160AREP222M10B0L05T"))
    )
    (comp (ref "C29")
      (value "10uF")
      (footprint "easyedapro:C1206")
      (libsource (lib "easyedapro") (part "CapAcitance"))
    )
    (comp (ref "C30")
      (value "10uF")
      (footprint "easyedapro:C1206")
      (libsource (lib "easyedapro") (part "CapAcitance"))
    )
    (comp (ref "C31")
      (value "1uF")
      (footprint "easyedapro:C1206")
      (libsource (lib "easyedapro") (part "CapAcitance"))
    )
    (comp (ref "C32")
      (value "100nF")
      (footprint "easyedapro:C1206")
      (libsource (lib "easyedapro") (part "CapAcitance"))
    )
    (comp (ref "C33")
      (value "100nF")
      (footprint "easyedapro:C1206")
      (libsource (lib "easyedapro") (part "CapAcitance"))
    )
    (comp (ref "D7")
      (value "1N4148W")
      (footprint "easyedapro:SOD-123F_L2.7-W1.6-LS3.8-RD")
      (description "二极管配置:独立式;正向压降(Vf):1V@50mA;直流反向耐压(Vr):75V;平均整流电流(Io):150mA;功率:400mW;反向恢复时间(trr):4ns;")
      (fields (field (name "Manufacturer") "ST(先科)"))
      (libsource (lib "easyedapro") (part "1N4148W_C81598"))
    )
    (comp (ref "D8")
      (value "SMBJ28CA")
      (footprint "easyedapro:SMB_L4.6-W3.6-LS5.3-BI")
      (description "反向截止电压(Vrwm):28V;最大钳位电压:45.4V;峰值脉冲电流(Ipp)@10/1000us:13.2A;击穿电压:31.1V;")
      (fields (field (name "Manufacturer") "JJW(捷捷微)"))
      (libsource (lib "easyedapro") (part "SMBJ28CA_C356756"))
    )
    (comp (ref "D10")
      (value "1N4148W")
      (footprint "easyedapro:SOD-123F_L2.7-W1.6-LS3.8-RD")
      (description "二极管配置:独立式;正向压降(Vf):1V@50mA;直流反向耐压(Vr):75V;平均整流电流(Io):150mA;功率:400mW;反向恢复时间(trr):4ns;")
      (fields (field (name "Manufacturer") "ST(先科)"))
      (libsource (lib "easyedapro") (part "1N4148W_C81598"))
    )
    (comp (ref "D13")
      (value "1N4148W")
      (footprint "easyedapro:SOD-123F_L2.7-W1.6-LS3.8-RD")
      (description "二极管配置:独立式;正向压降(Vf):1V@50mA;直流反向耐压(Vr):75V;平均整流电流(Io):150mA;功率:400mW;反向恢复时间(trr):4ns;")
      (fields (field (name "Manufacturer") "ST(先科)"))
      (libsource (lib "easyedapro") (part "1N4148W_C81598"))
    )
    (comp (ref "D15")
      (value "1N4148W")
      (footprint "easyedapro:SOD-123F_L2.7-W1.6-LS3.8-RD")
      (description "二极管配置:独立式;正向压降(Vf):1V@50mA;直流反向耐压(Vr):75V;平均整流电流(Io):150mA;功率:400mW;反向恢复时间(trr):4ns;")
      (fields (field (name "Manufacturer") "ST(先科)"))
      (libsource (lib "easyedapro") (part "1N4148W_C81598"))
    )
    (comp (ref "D21")
      (value "SMBJ36A")
      (footprint "easyedapro:SMB_L4.6-W3.6-LS5.3-RD")
      (description "反向截止电压(Vrwm):36V;最大钳位电压:58.1V;峰值脉冲电流(Ipp):10.3A;击穿电压:40V;")
      (fields (field (name "Manufacturer") "FMS(美丽微)"))
      (libsource (lib "easyedapro") (part "SMBJ36A_C143165"))
    )
    (comp (ref "Q2")
      (value "CSD18540Q5B")
      (footprint "easyedapro:VSON-CLIP-8_L5.0-W6.0-P1.27-BL")
      (fields (field (name "Manufacturer") "TI(德州仪器)"))
      (libsource (lib "easyedapro") (part "CSD18540Q5B"))
    )
    (comp (ref "Q3")
      (value "CSD18540Q5B")
      (footprint "easyedapro:VSON-CLIP-8_L5.0-W6.0-P1.27-BL")
      (fields (field (name "Manufacturer") "TI(德州仪器)"))
      (libsource (lib "easyedapro") (part "CSD18540Q5B"))
    )
    (comp (ref "Q4")
      (value "CSD18540Q5B")
      (footprint "easyedapro:VSON-CLIP-8_L5.0-W6.0-P1.27-BL")
      (fields (field (name "Manufacturer") "TI(德州仪器)"))
      (libsource (lib "easyedapro") (part "CSD18540Q5B"))
    )
    (comp (ref "Q5")
      (value "CSD18540Q5B")
      (footprint "easyedapro:VSON-CLIP-8_L5.0-W6.0-P1.27-BL")
      (fields (field (name "Manufacturer") "TI(德州仪器)"))
      (libsource (lib "easyedapro") (part "CSD18540Q5B"))
    )
    (comp (ref "R19") (value "10K") (footprint "easyedapro:R0603") (libsource (lib "easyedapro") (part "电阻")))
    (comp (ref "R20") (value "10R") (footprint "easyedapro:R0603") (libsource (lib "easyedapro") (part "电阻")))
    (comp (ref "R21") (value "10K") (footprint "easyedapro:R0603") (libsource (lib "easyedapro") (part "电阻")))
    (comp (ref "R22") (value "10K") (footprint "easyedapro:R0603") (libsource (lib "easyedapro") (part "电阻")))
    (comp (ref "R23") (value "10R") (footprint "easyedapro:R0603") (libsource (lib "easyedapro") (part "电阻")))
    (comp (ref "R24") (value "10K") (footprint "easyedapro:R0603") (libsource (lib "easyedapro") (part "电阻")))
    (comp (ref "R26") (value "10K") (footprint "easyedapro:R0603") (libsource (lib "easyedapro") (part "电阻")))
    (comp (ref "R27") (value "10R") (footprint "easyedapro:R0603") (libsource (lib "easyedapro") (part "电阻")))
    (comp (ref "R28") (value "10K") (footprint "easyedapro:R0603") (libsource (lib "easyedapro") (part "电阻")))
    (comp (ref "R29") (value "10K") (footprint "easyedapro:R0603") (libsource (lib "easyedapro") (part "电阻")))
    (comp (ref "R30") (value "10R") (footprint "easyedapro:R0603") (libsource (lib "easyedapro") (part "电阻")))
    (comp (ref "R31") (value "10K") (footprint "easyedapro:R0603") (libsource (lib "easyedapro") (part "电阻")))
    (comp (ref "U5")
      (value "SS56")
      (footprint "easyedapro:SMA_L4.2-W2.6-LS5.1-RD")
      (libsource (lib "easyedapro") (part "SS54_C9900023219"))
    )
    (comp (ref "U6")
      (value "22uH")
      (footprint "easyedapro:PQ2620_LL")
      (description "电感值:22uH;精度:±20%;饱和电流(Isat):28A;温升电流:23A")
      (fields (field (name "Manufacturer Part") "PQ2620-220M-D"))
      (libsource (lib "easyedapro") (part "PQ2620-220M"))
    )
    (comp (ref "U7")
      (value "UCC27282DR")
      (footprint "easyedapro:SOIC-8_L4.9-W3.9-P1.27-LS6.0-BL")
      (description "驱动配置:半桥;负载类型:MOSFET;驱动通道数:2;峰值灌电流:3.5A;峰值拉电流:2.5A;电源电压:5.5V~16V;上升时间:12ns;下降时间:10ns;")
      (fields (field (name "Manufacturer") "TI(德州仪器)"))
      (libsource (lib "easyedapro") (part "UCC27282DR"))
    )
    (comp (ref "U8")
      (value "SS56")
      (footprint "easyedapro:SMA_L4.2-W2.6-LS5.1-RD")
      (libsource (lib "easyedapro") (part "SS54_C9900023219"))
    )
    (comp (ref "U9")
      (value "SS56")
      (footprint "easyedapro:SMA_L4.2-W2.6-LS5.1-RD")
      (libsource (lib "easyedapro") (part "SS54_C9900023219"))
    )
    (comp (ref "U10")
      (value "UCC27282DR")
      (footprint "easyedapro:SOIC-8_L4.9-W3.9-P1.27-LS6.0-BL")
      (description "驱动配置:半桥;负载类型:MOSFET;驱动通道数:2;峰值灌电流:3.5A;峰值拉电流:2.5A;电源电压:5.5V~16V;上升时间:12ns;下降时间:10ns;")
      (fields (field (name "Manufacturer") "TI(德州仪器)"))
      (libsource (lib "easyedapro") (part "UCC27282DR"))
    )
    (comp (ref "U11")
      (value "SS56")
      (footprint "easyedapro:SMA_L4.2-W2.6-LS5.1-RD")
      (libsource (lib "easyedapro") (part "SS54_C9900023219"))
    )
    (comp (ref "C34")
      (value "100nF")
      (footprint "easyedapro:C1206")
      (libsource (lib "easyedapro") (part "CapAcitance"))
    )
    (comp (ref "C35")
      (value "C1206")
      (footprint "easyedapro:C1206")
      (libsource (lib "easyedapro") (part "CapAcitance"))
    )
    (comp (ref "C36")
      (value "10uF")
      (footprint "easyedapro:C1206")
      (libsource (lib "easyedapro") (part "CapAcitance"))
    )
    (comp (ref "C37")
      (value "1uF")
      (footprint "easyedapro:C1206")
      (libsource (lib "easyedapro") (part "CapAcitance"))
    )
    (comp (ref "C38")
      (value "2.2uF")
      (footprint "easyedapro:C1206")
      (libsource (lib "easyedapro") (part "CapAcitance"))
    )
    (comp (ref "C39")
      (value "100nF")
      (footprint "easyedapro:C1206")
      (libsource (lib "easyedapro") (part "CapAcitance"))
    )
    (comp (ref "C40")
      (value "10uF")
      (footprint "easyedapro:C1206")
      (libsource (lib "easyedapro") (part "CapAcitance"))
    )
    (comp (ref "C41")
      (value "1uF")
      (footprint "easyedapro:C1206")
      (libsource (lib "easyedapro") (part "CapAcitance"))
    )
    (comp (ref "C44")
      (value "47pF")
      (footprint "easyedapro:C1206")
      (libsource (lib "easyedapro") (part "CapAcitance"))
    )
    (comp (ref "C45")
      (value "4700pF=4.7nF")
      (footprint "easyedapro:C1206")
      (libsource (lib "easyedapro") (part "CapAcitance"))
    )
    (comp (ref "C46")
      (value "100nF")
      (footprint "easyedapro:C1206")
      (libsource (lib "easyedapro") (part "CapAcitance"))
    )
    (comp (ref "C47")
      (value "1uF")
      (footprint "easyedapro:C1206")
      (libsource (lib "easyedapro") (part "CapAcitance"))
    )
    (comp (ref "C48")
      (value "100nF")
      (footprint "easyedapro:C1206")
      (libsource (lib "easyedapro") (part "CapAcitance"))
    )
    (comp (ref "C49")
      (value "10uF")
      (footprint "easyedapro:C1206")
      (libsource (lib "easyedapro") (part "CapAcitance"))
    )
    (comp (ref "C56")
      (value "100nF")
      (footprint "easyedapro:C1206")
      (libsource (lib "easyedapro") (part "CapAcitance"))
    )
    (comp (ref "C57")
      (value "C1206")
      (footprint "easyedapro:C1206")
      (libsource (lib "easyedapro") (part "CapAcitance"))
    )
    (comp (ref "C62")
      (value "10uF")
      (footprint "easyedapro:C1206")
      (libsource (lib "easyedapro") (part "CapAcitance"))
    )
    (comp (ref "C63")
      (value "1uF")
      (footprint "easyedapro:C1206")
      (libsource (lib "easyedapro") (part "CapAcitance"))
    )
    (comp (ref "C66")
      (value "47pF")
      (footprint "easyedapro:C1206")
      (libsource (lib "easyedapro") (part "CapAcitance"))
    )
    (comp (ref "C67")
      (value "4700pF=4.7nF")
      (footprint "easyedapro:C1206")
      (libsource (lib "easyedapro") (part "CapAcitance"))
    )
    (comp (ref "D16")
      (value "DSK36")
      (footprint "easyedapro:SOD-123FL_L2.8-W1.8-LS3.7-R-RD")
      (description "二极管配置:独立式;正向压降(Vf):700mV@3A;直流反向耐压(Vr):60V;整流电流:3A;")
      (fields (field (name "Manufacturer") "TWGMC(台湾迪嘉)"))
      (libsource (lib "easyedapro") (part "DSK36_C727077"))
    )
    (comp (ref "D20")
      (value "DSK36")
      (footprint "easyedapro:SOD-123FL_L2.8-W1.8-LS3.7-R-RD")
      (description "二极管配置:独立式;正向压降(Vf):700mV@3A;直流反向耐压(Vr):60V;整流电流:3A;")
      (fields (field (name "Manufacturer") "TWGMC(台湾迪嘉)"))
      (libsource (lib "easyedapro") (part "DSK36_C727077"))
    )
    (comp (ref "F1")
      (value "BSMD1206-035-16V")
      (footprint "easyedapro:F1206")
      (description "最大电压:16V;最大电流:40A;保持电流:350mA;跳闸电流:750mA;")
      (fields (field (name "Manufacturer") "BHFUSE(佰宏)"))
      (libsource (lib "easyedapro") (part "BSMD1206-035-16V"))
    )
    (comp (ref "FB1")
      (value "GZ1608D601TF")
      (footprint "easyedapro:L0603")
      (description "标称阻抗@测试频率:600Ω@100MHz;误差:±25%;直流电阻(RDC):450mΩ;")
      (fields (field (name "Manufacturer") "Sunlord(顺络)"))
      (libsource (lib "easyedapro") (part "GZ1608D601TF"))
    )
    (comp (ref "L2")
      (value "10uH")
      (footprint "easyedapro:IND-SMD_L7.8-W7.0_MAPM0630F")
      (fields (field (name "Manufacturer Part") "0650-10UH"))
      (libsource (lib "easyedapro") (part "0650-2.2UH"))
    )
    (comp (ref "L4")
      (value "10uH")
      (footprint "easyedapro:IND-SMD_L7.8-W7.0_MAPM0630F")
      (fields (field (name "Manufacturer Part") "0650-10UH"))
      (libsource (lib "easyedapro") (part "0650-2.2UH"))
    )
    (comp (ref "R32") (value "50K") (footprint "easyedapro:R0603") (libsource (lib "easyedapro") (part "电阻")))
    (comp (ref "R33")
      (value "588K")
      (footprint "easyedapro:R0603")
      (libsource (lib "easyedapro") (part "电阻"))
    )
    (comp (ref "R34")
      (value "16.9K")
      (footprint "easyedapro:R0603")
      (libsource (lib "easyedapro") (part "电阻"))
    )
    (comp (ref "R35")
      (value "100K")
      (footprint "easyedapro:R0603")
      (libsource (lib "easyedapro") (part "电阻"))
    )
    (comp (ref "R36") (value "10K") (footprint "easyedapro:R0603") (libsource (lib "easyedapro") (part "电阻")))
    (comp (ref "R37")
      (value "132.7K")
      (footprint "easyedapro:R0603")
      (libsource (lib "easyedapro") (part "电阻"))
    )
    (comp (ref "R40")
      (value "120K")
      (footprint "easyedapro:R0603")
      (libsource (lib "easyedapro") (part "电阻"))
    )
    (comp (ref "R41")
      (value "588K")
      (footprint "easyedapro:R0603")
      (libsource (lib "easyedapro") (part "电阻"))
    )
    (comp (ref "R42")
      (value "16.9K")
      (footprint "easyedapro:R0603")
      (libsource (lib "easyedapro") (part "电阻"))
    )
    (comp (ref "R43")
      (value "100K")
      (footprint "easyedapro:R0603")
      (libsource (lib "easyedapro") (part "电阻"))
    )
    (comp (ref "R44") (value "10K") (footprint "easyedapro:R0603") (libsource (lib "easyedapro") (part "电阻")))
    (comp (ref "R45")
      (value "61.3K")
      (footprint "easyedapro:R0603")
      (libsource (lib "easyedapro") (part "电阻"))
    )
    (comp (ref "U12")
      (value "SMD0805-200 1.1A 2.2A 6V")
      (footprint "easyedapro:F0805")
      (libsource (lib "easyedapro") (part "SMD0805-200 2A 30V"))
    )
    (comp (ref "U13")
      (value "TPS54560DDAR/TPS54360")
      (footprint "easyedapro:SOIC-8_L5.0-W4.0-P1.27-LS6.0-BL-EP2.0")
      (description "功能类型:降压型;输出类型:可调;工作电压:4.5V~60V;输出电压:800mV~58.8V;输出电流:5A;")
      (fields (field (name "Manufacturer") "TI(德州仪器)"))
      (libsource (lib "easyedapro") (part "TPS54560DDAR"))
    )
    (comp (ref "U14")
      (value "10V 470uF")
      (footprint "easyedapro:CAP-SMD_BD6.3-L6.6-W6.6-LS7.2-FD")
      (description "容值:47uF;精度:±20%;额定电压:50V;纹波电流:63mA@120Hz;等效串联电阻:-;")
      (fields
        (field (name "Manufacturer Part") "CS47UF50V167RV0158")
        (field (name "Manufacturer") "KNSCHA(科尼盛)")
      )
      (libsource (lib "easyedapro") (part "cs47uf50v167rv0158"))
    )
    (comp (ref "U16")
      (value "~")
      (footprint "easyedapro:SOT-89-3_L4.5-W2.5-P1.50-LS4.2-BR")
      (description "输出类型:-;")
      (fields (field (name "Manufacturer Part") "AMS1117-3.3") (field (name "Manufacturer") "Slkor(萨科微)"))
      (libsource (lib "easyedapro") (part "AMS1117-3.3_C880752"))
    )
    (comp (ref "U17")
      (value "50V 47uF")
      (footprint "easyedapro:CAP-SMD_BD6.3-L6.6-W6.6-LS7.2-FD")
      (description "容值:47uF;精度:±20%;额定电压:50V;纹波电流:63mA@120Hz;等效串联电阻:-;")
      (fields
        (field (name "Manufacturer Part") "CS47UF50V167RV0158")
        (field (name "Manufacturer") "KNSCHA(科尼盛)")
      )
      (libsource (lib "easyedapro") (part "cs47uf50v167rv0158"))
    )
    (comp (ref "U18")
      (value "LC-LL-34 3.6V")
      (footprint "easyedapro:LL-34_L3.5-W1.5-RD")
      (libsource (lib "easyedapro") (part "LC-LL-34"))
    )
    (comp (ref "U19")
      (value "LC-LL-34 5.1V")
      (footprint "easyedapro:LL-34_L3.5-W1.5-RD")
      (libsource (lib "easyedapro") (part "LC-LL-34"))
    )
    (comp (ref "U21")
      (value "TPS54560DDAR/TPS54360")
      (footprint "easyedapro:SOIC-8_L5.0-W4.0-P1.27-LS6.0-BL-EP2.0")
      (description "功能类型:降压型;输出类型:可调;工作电压:4.5V~60V;输出电压:800mV~58.8V;输出电流:5A;")
      (fields (field (name "Manufacturer") "TI(德州仪器)"))
      (libsource (lib "easyedapro") (part "TPS54560DDAR"))
    )
    (comp (ref "U22")
      (value "16V 220uf")
      (footprint "easyedapro:CAP-SMD_BD6.3-L6.6-W6.6-LS7.2-FD")
      (description "容值:47uF;精度:±20%;额定电压:50V;纹波电流:63mA@120Hz;等效串联电阻:-;")
      (fields
        (field (name "Manufacturer Part") "CS47UF50V167RV0158")
        (field (name "Manufacturer") "KNSCHA(科尼盛)")
      )
      (libsource (lib "easyedapro") (part "cs47uf50v167rv0158"))
    )
    (comp (ref "C68")
      (value "100nF")
      (footprint "easyedapro:C1206")
      (libsource (lib "easyedapro") (part "CapAcitance"))
    )
    (comp (ref "C69")
      (value "NC")
      (footprint "easyedapro:C1206")
      (libsource (lib "easyedapro") (part "CapAcitance"))
    )
    (comp (ref "C70")
      (value "100nF")
      (footprint "easyedapro:C1206")
      (libsource (lib "easyedapro") (part "CapAcitance"))
    )
    (comp (ref "C71")
      (value "NC")
      (footprint "easyedapro:C1206")
      (libsource (lib "easyedapro") (part "CapAcitance"))
    )
    (comp (ref "C72")
      (value "100nF")
      (footprint "easyedapro:C1206")
      (libsource (lib "easyedapro") (part "CapAcitance"))
    )
    (comp (ref "C73")
      (value "NC")
      (footprint "easyedapro:C1206")
      (libsource (lib "easyedapro") (part "CapAcitance"))
    )
    (comp (ref "C74")
      (value "1nF")
      (footprint "easyedapro:C1206")
      (libsource (lib "easyedapro") (part "CapAcitance"))
    )
    (comp (ref "C75")
      (value "NC")
      (footprint "easyedapro:C1206")
      (libsource (lib "easyedapro") (part "CapAcitance"))
    )
    (comp (ref "C76")
      (value "100nF")
      (footprint "easyedapro:C1206")
      (libsource (lib "easyedapro") (part "CapAcitance"))
    )
    (comp (ref "C77")
      (value "100nF")
      (footprint "easyedapro:C1206")
      (libsource (lib "easyedapro") (part "CapAcitance"))
    )
    (comp (ref "C78")
      (value "NC")
      (footprint "easyedapro:C1206")
      (libsource (lib "easyedapro") (part "CapAcitance"))
    )
    (comp (ref "C79")
      (value "NC")
      (footprint "easyedapro:C1206")
      (libsource (lib "easyedapro") (part "CapAcitance"))
    )
    (comp (ref "C80")
      (value "100nF")
      (footprint "easyedapro:C1206")
      (libsource (lib "easyedapro") (part "CapAcitance"))
    )
    (comp (ref "C81")
      (value "NC")
      (footprint "easyedapro:C1206")
      (libsource (lib "easyedapro") (part "CapAcitance"))
    )
    (comp (ref "C82")
      (value "1nF")
      (footprint "easyedapro:C1206")
      (libsource (lib "easyedapro") (part "CapAcitance"))
    )
    (comp (ref "C83")
      (value "NC")
      (footprint "easyedapro:C1206")
      (libsource (lib "easyedapro") (part "CapAcitance"))
    )
    (comp (ref "C84")
      (value "100nF")
      (footprint "easyedapro:C1206")
      (libsource (lib "easyedapro") (part "CapAcitance"))
    )
    (comp (ref "C85")
      (value "NC")
      (footprint "easyedapro:C1206")
      (libsource (lib "easyedapro") (part "CapAcitance"))
    )
    (comp (ref "C86")
      (value "NC")
      (footprint "easyedapro:C1206")
      (libsource (lib "easyedapro") (part "CapAcitance"))
    )
    (comp (ref "C87")
      (value "100nF")
      (footprint "easyedapro:C1206")
      (libsource (lib "easyedapro") (part "CapAcitance"))
    )
    (comp (ref "C88")
      (value "NC")
      (footprint "easyedapro:C1206")
      (libsource (lib "easyedapro") (part "CapAcitance"))
    )
    (comp (ref "C89")
      (value "NC")
      (footprint "easyedapro:C1206")
      (libsource (lib "easyedapro") (part "CapAcitance"))
    )
    (comp (ref "C90")
      (value "100nF")
      (footprint "easyedapro:C1206")
      (libsource (lib "easyedapro") (part "CapAcitance"))
    )
    (comp (ref "C91")
      (value "100nF")
      (footprint "easyedapro:C1206")
      (libsource (lib "easyedapro") (part "CapAcitance"))
    )
    (comp (ref "R46") (value "47R") (footprint "easyedapro:R0603") (libsource (lib "easyedapro") (part "电阻")))
    (comp (ref "R47")
      (value "3K 0.1%")
      (footprint "easyedapro:R0603")
      (libsource (lib "easyedapro") (part "电阻"))
    )
    (comp (ref "R48")
      (value "5.1R")
      (footprint "easyedapro:R0603")
      (libsource (lib "easyedapro") (part "电阻"))
    )
    (comp (ref "R49")
      (value "30K 0.1%")
      (footprint "easyedapro:R0603")
      (libsource (lib "easyedapro") (part "电阻"))
    )
    (comp (ref "R50") (value "47R") (footprint "easyedapro:R0603") (libsource (lib "easyedapro") (part "电阻")))
    (comp (ref "R51")
      (value "5.1R")
      (footprint "easyedapro:R0603")
      (libsource (lib "easyedapro") (part "电阻"))
    )
    (comp (ref "R52")
      (value "30K 0.1%")
      (footprint "easyedapro:R0603")
      (libsource (lib "easyedapro") (part "电阻"))
    )
    (comp (ref "R53")
      (value "3K 0.1%")
      (footprint "easyedapro:R0603")
      (libsource (lib "easyedapro") (part "电阻"))
    )
    (comp (ref "R54") (value "47R") (footprint "easyedapro:R0603") (libsource (lib "easyedapro") (part "电阻")))
    (comp (ref "R55")
      (value "3K 0.1%")
      (footprint "easyedapro:R0603")
      (libsource (lib "easyedapro") (part "电阻"))
    )
    (comp (ref "R56")
      (value "30K 0.1%")
      (footprint "easyedapro:R0603")
      (libsource (lib "easyedapro") (part "电阻"))
    )
    (comp (ref "R57") (value "47R") (footprint "easyedapro:R0603") (libsource (lib "easyedapro") (part "电阻")))
    (comp (ref "R58")
      (value "5.1R")
      (footprint "easyedapro:R0603")
      (libsource (lib "easyedapro") (part "电阻"))
    )
    (comp (ref "R59")
      (value "30K 0.1%")
      (footprint "easyedapro:R0603")
      (libsource (lib "easyedapro") (part "电阻"))
    )
    (comp (ref "R60")
      (value "3K 0.1%")
      (footprint "easyedapro:R0603")
      (libsource (lib "easyedapro") (part "电阻"))
    )
    (comp (ref "R61")
      (value "5.1R")
      (footprint "easyedapro:R0603")
      (libsource (lib "easyedapro") (part "电阻"))
    )
    (comp (ref "R62") (value "47R") (footprint "easyedapro:R0603") (libsource (lib "easyedapro") (part "电阻")))
    (comp (ref "R63")
      (value "5.1R")
      (footprint "easyedapro:R0603")
      (libsource (lib "easyedapro") (part "电阻"))
    )
    (comp (ref "R64")
      (value "2mΩ")
      (footprint "easyedapro:RES-SMD_L6.3-W3.3_HOLR2512")
      (description "电阻类型:-;阻值:2mΩ;精度:±1%;额定压降:-;功率:3W;温度系数:±50ppm/°C;安装方式:-;")
      (fields
        (field (name "Manufacturer Part") "SD2512FR002E3WPKH")
        (field (name "Manufacturer") "Sunway(信维通信)")
      )
      (libsource (lib "easyedapro") (part "SD2512FR002E3WPKH"))
    )
    (comp (ref "R65")
      (value "5.1R")
      (footprint "easyedapro:R0603")
      (libsource (lib "easyedapro") (part "电阻"))
    )
    (comp (ref "U24")
      (value "REF3033AIDBZR")
      (footprint "easyedapro:SOT-23-3_L3.0-W1.7-P0.95-LS2.9-BR")
      (description "输出类型:固定;输入电压:3.35V~5.5V;输出电压:3.3V;输出电流:25mA;精度:±0.2%;")
      (fields (field (name "Manufacturer") "TI(德州仪器)"))
      (libsource (lib "easyedapro") (part "REF3033AIDBZR"))
    )
    (comp (ref "U25")
      (value "INA240A1PWR")
      (footprint "easyedapro:TSSOP-8_L4.4-W3.0-P0.65-LS6.4-BL")
      (description "放大器数:单路;")
      (fields (field (name "Manufacturer") "TI(德州仪器)"))
      (libsource (lib "easyedapro") (part "INA240A1PWR"))
    )
    (comp (ref "U26")
      (value "0R010/1%3W/R2512")
      (footprint "easyedapro:R2512")
      (libsource (lib "easyedapro") (part "0R005/1%3W/R2512"))
    )
    (comp (ref "U27")
      (value "INA240A1PWR")
      (footprint "easyedapro:TSSOP-8_L4.4-W3.0-P0.65-LS6.4-BL")
      (description "放大器数:单路;")
      (fields (field (name "Manufacturer") "TI(德州仪器)"))
      (libsource (lib "easyedapro") (part "INA240A1PWR"))
    )
    (comp (ref "U28")
      (value "0R005/1%3W/R2512")
      (footprint "easyedapro:R2512")
      (libsource (lib "easyedapro") (part "0R005/1%3W/R2512"))
    )
    (comp (ref "U29")
      (value "INA240A1PWR")
      (footprint "easyedapro:TSSOP-8_L4.4-W3.0-P0.65-LS6.4-BL")
      (description "放大器数:单路;")
      (fields (field (name "Manufacturer") "TI(德州仪器)"))
      (libsource (lib "easyedapro") (part "INA240A1PWR"))
    )
    (comp (ref "U31")
      (value "OPA2365AIDR")
      (footprint "easyedapro:SOIC-8_L4.9-W3.9-P1.27-LS6.0-BL")
      (description "放大器数:双路;增益带宽积(GBP):50MHz;输入偏置电流(Ib):0.2pA;输入失调电压(Vos):100uV;压摆率(SR):25V/us;带宽(-3db):-;轨到轨:-;")
      (fields (field (name "Manufacturer") "TI(德州仪器)"))
      (libsource (lib "easyedapro") (part "OPA2365AIDR"))
    )
    (comp (ref "Battery")
      (value "XT30U-M")
      (footprint "easyedapro:CONN-TH_XT30U-M")
      (description "类别:-;类型1:-;")
      (fields (field (name "Manufacturer") "AMASS(艾迈斯)"))
      (libsource (lib "easyedapro") (part "XT30U-M"))
    )
    (comp (ref "C92")
      (value "50V 470uF")
      (footprint "easyedapro:CAP-TH_BD10.0-P5.00-D0.6-FD-A")
      (fields
        (field (name "Manufacturer Part") "160AREP222M10B0L05T")
        (field (name "Manufacturer") "APAQ(钰邦)")
      )
      (libsource (lib "easyedapro") (part "160AREP222M10B0L05T"))
    )
    (comp (ref "C93")
      (value "50V 470uF")
      (footprint "easyedapro:CAP-TH_BD10.0-P5.00-D0.6-FD-A")
      (fields
        (field (name "Manufacturer Part") "160AREP222M10B0L05T")
        (field (name "Manufacturer") "APAQ(钰邦)")
      )
      (libsource (lib "easyedapro") (part "160AREP222M10B0L05T"))
    )
    (comp (ref "Cap")
      (value "XT30U-M")
      (footprint "easyedapro:CONN-TH_XT30U-M")
      (description "类别:-;类型1:-;")
      (fields (field (name "Manufacturer") "AMASS(艾迈斯)"))
      (libsource (lib "easyedapro") (part "XT30U-M"))
    )
    (comp (ref "Chassis")
      (value "XT30U-M")
      (footprint "easyedapro:CONN-TH_XT30U-M")
      (description "类别:-;类型1:-;")
      (fields (field (name "Manufacturer") "AMASS(艾迈斯)"))
      (libsource (lib "easyedapro") (part "XT30U-M"))
    )
    (comp (ref "M1")
      (value "M3")
      (footprint "easyedapro:M3_cut_out")
      (description "M3_隔离电气连接")
      (libsource (lib "easyedapro") (part "M*_cut_out"))
    )
    (comp (ref "M2")
      (value "M3")
      (footprint "easyedapro:M3_cut_out")
      (description "M3_隔离电气连接")
      (libsource (lib "easyedapro") (part "M*_cut_out"))
    )
    (comp (ref "M3")
      (value "M3")
      (footprint "easyedapro:M3_cut_out")
      (description "M3_隔离电气连接")
      (libsource (lib "easyedapro") (part "M*_cut_out"))
    )
    (comp (ref "M4")
      (value "M3")
      (footprint "easyedapro:M3_cut_out")
      (description "M3_隔离电气连接")
      (libsource (lib "easyedapro") (part "M*_cut_out"))
    )
    (comp (ref "U30")
      (value "~")
      (footprint "easyedapro:JLC-QRCODE-8x8")
      (libsource (lib "easyedapro") (part "嘉立创二维码8x8"))
    )
  )
  (nets
    (net (code "1") (name "+3.3V") (class "Default")
      (node (ref "BUZZER1") (pin "1") (pinfunction "+_1") (pintype "input"))
      (node (ref "C1") (pin "2") (pinfunction "2_2") (pintype "input"))
      (node (ref "C14") (pin "1") (pinfunction "1_1") (pintype "input"))
      (node (ref "C15") (pin "1") (pinfunction "1_1") (pintype "input"))
      (node (ref "C16") (pin "2") (pinfunction "2_2") (pintype "input"))
      (node (ref "C2") (pin "2") (pinfunction "2_2") (pintype "input"))
      (node (ref "C46") (pin "2") (pinfunction "2_2") (pintype "input"))
      (node (ref "C47") (pin "2") (pinfunction "2_2") (pintype "input"))
      (node (ref "C6") (pin "2") (pinfunction "2_2") (pintype "input"))
      (node (ref "C7") (pin "2") (pinfunction "2_2") (pintype "input"))
      (node (ref "C70") (pin "2") (pinfunction "2_2") (pintype "input"))
      (node (ref "C76") (pin "2") (pinfunction "2_2") (pintype "input"))
      (node (ref "C77") (pin "2") (pinfunction "2_2") (pintype "input"))
      (node (ref "C84") (pin "2") (pinfunction "2_2") (pintype "input"))
      (node (ref "C9") (pin "2") (pinfunction "2_2") (pintype "input"))
      (node (ref "C90") (pin "2") (pinfunction "2_2") (pintype "input"))
      (node (ref "C91") (pin "2") (pinfunction "2_2") (pintype "input"))
      (node (ref "D3") (pin "2") (pinfunction "2_2") (pintype "input"))
      (node (ref "GH1") (pin "4") (pinfunction "4_4") (pintype "input"))
      (node (ref "GH2") (pin "4") (pinfunction "4_4") (pintype "input"))
      (node (ref "LED1") (pin "1") (pinfunction "A_1") (pintype "input"))
      (node (ref "LED2") (pin "1") (pinfunction "A_1") (pintype "input"))
      (node (ref "LED3") (pin "1") (pinfunction "A_1") (pintype "input"))
      (node (ref "R7") (pin "2") (pinfunction "2_2") (pintype "input"))
      (node (ref "SWD1") (pin "4") (pinfunction "4_4") (pintype "input"))
      (node (ref "U1") (pin "1") (pinfunction "VBAT_1") (pintype "input"))
      (node (ref "U1") (pin "16") (pinfunction "VDD_16") (pintype "input"))
      (node (ref "U1") (pin "29") (pinfunction "VDDA_29") (pintype "input"))
      (node (ref "U1") (pin "32") (pinfunction "VDD_32") (pintype "input"))
      (node (ref "U1") (pin "48") (pinfunction "VDD_48") (pintype "input"))
      (node (ref "U1") (pin "64") (pinfunction "VDD_64") (pintype "input"))
      (node (ref "U16") (pin "2") (pinfunction "VOUT_2") (pintype "input"))
      (node (ref "U18") (pin "1") (pinfunction "K_1") (pintype "unspecified"))
      (node (ref "U25") (pin "5") (pinfunction "VS_5") (pintype "input"))
      (node (ref "U27") (pin "5") (pinfunction "VS_5") (pintype "input"))
      (node (ref "U29") (pin "5") (pinfunction "VS_5") (pintype "input"))
      (node (ref "U31") (pin "8") (pinfunction "V+_8") (pintype "unspecified"))
    )
    (net (code "2") (name "+5V") (class "Default")
      (node (ref "C12") (pin "2") (pinfunction "2_2") (pintype "input"))
      (node (ref "C48") (pin "2") (pinfunction "2_2") (pintype "input"))
      (node (ref "C49") (pin "2") (pinfunction "2_2") (pintype "input"))
      (node (ref "C68") (pin "2") (pinfunction "2_2") (pintype "input"))
      (node (ref "D1") (pin "5") (pinfunction "VCC_5") (pintype "unspecified"))
      (node (ref "D2") (pin "5") (pinfunction "VCC_5") (pintype "unspecified"))
      (node (ref "FB1") (pin "1") (pinfunction "1_1") (pintype "input"))
      (node (ref "U16") (pin "3") (pinfunction "VIN_3") (pintype "input"))
      (node (ref "U19") (pin "1") (pinfunction "K_1") (pintype "unspecified"))
      (node (ref "U24") (pin "1") (pinfunction "IN_1") (pintype "unspecified"))
      (node (ref "U3") (pin "3") (pinfunction "VCC_3") (pintype "input"))
    )
    (net (code "3") (name "12V") (class "Default")
      (node (ref "C17") (pin "2") (pinfunction "2_2") (pintype "input"))
      (node (ref "C18") (pin "2") (pinfunction "2_2") (pintype "input"))
      (node (ref "C19") (pin "2") (pinfunction "2_2") (pintype "input"))
      (node (ref "C26") (pin "2") (pinfunction "2_2") (pintype "input"))
      (node (ref "C31") (pin "2") (pinfunction "2_2") (pintype "input"))
      (node (ref "C32") (pin "2") (pinfunction "2_2") (pintype "input"))
      (node (ref "F1") (pin "2") (pinfunction "2_2") (pintype "unspecified"))
      (node (ref "U10") (pin "1") (pinfunction "VDD_1") (pintype "unspecified"))
      (node (ref "U7") (pin "1") (pinfunction "VDD_1") (pintype "unspecified"))
    )
    (net (code "4") (name "24V") (class "Default")
      (node (ref "C21") (pin "1") (pinfunction "1_1") (pintype "input"))
      (node (ref "C22") (pin "1") (pinfunction "1_1") (pintype "input"))
      (node (ref "C24") (pin "2") (pinfunction "2_2") (pintype "input"))
      (node (ref "C25") (pin "2") (pinfunction "2_2") (pintype "input"))
      (node (ref "C40") (pin "2") (pinfunction "2_2") (pintype "input"))
      (node (ref "C41") (pin "2") (pinfunction "2_2") (pintype "input"))
      (node (ref "C62") (pin "2") (pinfunction "2_2") (pintype "input"))
      (node (ref "C63") (pin "2") (pinfunction "2_2") (pintype "input"))
      (node (ref "D8") (pin "2") (pinfunction "A_2") (pintype "unspecified"))
      (node (ref "Q2") (pin "5") (pinfunction "D_5") (pintype "unspecified"))
      (node (ref "Q2") (pin "6") (pinfunction "D_6") (pintype "unspecified"))
      (node (ref "Q2") (pin "7") (pinfunction "D_7") (pintype "unspecified"))
      (node (ref "Q2") (pin "8") (pinfunction "D_8") (pintype "unspecified"))
      (node (ref "R33") (pin "2") (pinfunction "2_2") (pintype "input"))
      (node (ref "R41") (pin "2") (pinfunction "2_2") (pintype "input"))
      (node (ref "R51") (pin "1") (pinfunction "1_1") (pintype "input"))
      (node (ref "R58") (pin "1") (pinfunction "1_1") (pintype "input"))
      (node (ref "R59") (pin "1") (pinfunction "1_1") (pintype "input"))
      (node (ref "U13") (pin "2") (pinfunction "VIN_2") (pintype "unspecified"))
      (node (ref "U17") (pin "1") (pinfunction "1_1") (pintype "input"))
      (node (ref "U21") (pin "2") (pinfunction "VIN_2") (pintype "unspecified"))
      (node (ref "U26") (pin "1") (pinfunction "1_1") (pintype "input"))
      (node (ref "U28") (pin "2") (pinfunction "2_2") (pintype "input"))
      (node (ref "U5") (pin "1") (pinfunction "C_1") (pintype "unspecified"))
    )
    (net (code "5") (name "ADC3_IN1") (class "Default")
      (node (ref "C82") (pin "2") (pinfunction "2_2") (pintype "input"))
      (node (ref "R57") (pin "2") (pinfunction "2_2") (pintype "input"))
      (node (ref "U1") (pin "25") (pinfunction "PB1_25") (pintype "input"))
    )
    (net (code "6") (name "ADC4_IN3") (class "Default")
      (node (ref "U1") (pin "34") (pinfunction "PB12_34") (pintype "input"))
    )
    (net (code "7") (name "ADC4_IN4") (class "Default")
      (node (ref "C74") (pin "2") (pinfunction "2_2") (pintype "input"))
      (node (ref "R50") (pin "2") (pinfunction "2_2") (pintype "input"))
      (node (ref "U1") (pin "36") (pinfunction "PB14_36") (pintype "input"))
    )
    (net (code "8") (name "AGND") (class "Default")
      (node (ref "C68") (pin "1") (pinfunction "1_1") (pintype "input"))
      (node (ref "C69") (pin "2") (pinfunction "2_2") (pintype "input"))
      (node (ref "C72") (pin "2") (pinfunction "2_2") (pintype "input"))
      (node (ref "C76") (pin "1") (pinfunction "1_1") (pintype "input"))
      (node (ref "C77") (pin "1") (pinfunction "1_1") (pintype "input"))
      (node (ref "C78") (pin "2") (pinfunction "2_2") (pintype "input"))
      (node (ref "C80") (pin "2") (pinfunction "2_2") (pintype "input"))
      (node (ref "C84") (pin "1") (pinfunction "1_1") (pintype "input"))
      (node (ref "C85") (pin "2") (pinfunction "2_2") (pintype "input"))
      (node (ref "C87") (pin "2") (pinfunction "2_2") (pintype "input"))
      (node (ref "C90") (pin "1") (pinfunction "1_1") (pintype "input"))
      (node (ref "C91") (pin "1") (pinfunction "1_1") (pintype "input"))
      (node (ref "R6") (pin "2") (pinfunction "2_2") (pintype "input"))
      (node (ref "R66") (pin "2") (pinfunction "2_2") (pintype "input"))
      (node (ref "U24") (pin "3") (pinfunction "GND_3") (pintype "unspecified"))
      (node (ref "U25") (pin "4") (pinfunction "GND_4") (pintype "input"))
      (node (ref "U25") (pin "7") (pinfunction "REF1_7") (pintype "input"))
      (node (ref "U27") (pin "4") (pinfunction "GND_4") (pintype "input"))
      (node (ref "U27") (pin "7") (pinfunction "REF1_7") (pintype "input"))
      (node (ref "U29") (pin "4") (pinfunction "GND_4") (pintype "input"))
      (node (ref "U29") (pin "7") (pinfunction "REF1_7") (pintype "input"))
    )
    (net (code "9") (name "BAT") (class "Default")
      (node (ref "Battery") (pin "1") (pinfunction "1_1") (pintype "input"))
      (node (ref "R48") (pin "1") (pinfunction "1_1") (pintype "input"))
      (node (ref "U26") (pin "2") (pinfunction "2_2") (pintype "input"))
    )
    (net (code "10") (name "BUZZ") (class "Default")
      (node (ref "R14") (pin "1") (pinfunction "1_1") (pintype "input"))
      (node (ref "U1") (pin "14") (pinfunction "PA2_14") (pintype "input"))
    )
    (net (code "11") (name "CAN1_RX") (class "Default")
      (node (ref "D1") (pin "3") (pinfunction "I/O_3") (pintype "unspecified"))
      (node (ref "R8") (pin "2") (pinfunction "2_2") (pintype "input"))
      (node (ref "U1") (pin "61") (pinfunction "PB8-BOOT0_61") (pintype "input"))
    )
    (net (code "12") (name "CAN1_TX") (class "Default")
      (node (ref "D1") (pin "4") (pinfunction "I/O_4") (pintype "unspecified"))
      (node (ref "U1") (pin "62") (pinfunction "PB9_62") (pintype "input"))
      (node (ref "U3") (pin "1") (pinfunction "TXD_1") (pintype "input"))
    )
    (net (code "13") (name "CLK") (class "Default")
      (node (ref "D2") (pin "4") (pinfunction "I/O_4") (pintype "unspecified"))
      (node (ref "R4") (pin "2") (pinfunction "2_2") (pintype "input"))
      (node (ref "U1") (pin "50") (pinfunction "PA14_50") (pintype "input"))
    )
    (net (code "14") (name "Cap_B") (class "Default")
      (node (ref "Cap") (pin "1") (pinfunction "1_1") (pintype "input"))
      (node (ref "R64") (pin "1") (pinfunction "1_1") (pintype "unspecified"))
      (node (ref "R65") (pin "1") (pinfunction "1_1") (pintype "input"))
    )
    (net (code "15") (name "Cap_Front") (class "Default")
      (node (ref "C27") (pin "1") (pinfunction "1_1") (pintype "input"))
      (node (ref "C29") (pin "2") (pinfunction "2_2") (pintype "input"))
      (node (ref "C30") (pin "2") (pinfunction "2_2") (pintype "input"))
      (node (ref "D21") (pin "1") (pinfunction "K_1") (pintype "unspecified"))
      (node (ref "Q4") (pin "5") (pinfunction "D_5") (pintype "unspecified"))
      (node (ref "Q4") (pin "6") (pinfunction "D_6") (pintype "unspecified"))
      (node (ref "Q4") (pin "7") (pinfunction "D_7") (pintype "unspecified"))
      (node (ref "Q4") (pin "8") (pinfunction "D_8") (pintype "unspecified"))
      (node (ref "R52") (pin "1") (pinfunction "1_1") (pintype "input"))
      (node (ref "R63") (pin "1") (pinfunction "1_1") (pintype "input"))
      (node (ref "R64") (pin "2") (pinfunction "2_2") (pintype "unspecified"))
      (node (ref "U9") (pin "1") (pinfunction "C_1") (pintype "unspecified"))
    )
    (net (code "16") (name "Chassis_current") (class "Default")
      (node (ref "C92") (pin "1") (pinfunction "1_1") (pintype "input"))
      (node (ref "C93") (pin "1") (pinfunction "1_1") (pintype "input"))
      (node (ref "Chassis") (pin "1") (pinfunction "1_1") (pintype "input"))
      (node (ref "R61") (pin "1") (pinfunction "1_1") (pintype "input"))
      (node (ref "U28") (pin "1") (pinfunction "1_1") (pintype "input"))
    )
    (net (code "17") (name "DIO") (class "Default")
      (node (ref "D2") (pin "3") (pinfunction "I/O_3") (pintype "unspecified"))
      (node (ref "R3") (pin "2") (pinfunction "2_2") (pintype "input"))
      (node (ref "U1") (pin "49") (pinfunction "PA13_49") (pintype "input"))
    )
    (net (code "18") (name "GND") (class "Default")
      (node (ref "Battery") (pin "2") (pinfunction "2_2") (pintype "input"))
      (node (ref "C1") (pin "1") (pinfunction "1_1") (pintype "input"))
      (node (ref "C10") (pin "2") (pinfunction "2_2") (pintype "input"))
      (node (ref "C11") (pin "2") (pinfunction "2_2") (pintype "input"))
      (node (ref "C12") (pin "1") (pinfunction "1_1") (pintype "input"))
      (node (ref "C13") (pin "1") (pinfunction "1_1") (pintype "input"))
      (node (ref "C14") (pin "2") (pinfunction "2_2") (pintype "input"))
      (node (ref "C15") (pin "2") (pinfunction "2_2") (pintype "input"))
      (node (ref "C16") (pin "1") (pinfunction "1_1") (pintype "input"))
      (node (ref "C17") (pin "1") (pinfunction "1_1") (pintype "input"))
      (node (ref "C18") (pin "1") (pinfunction "1_1") (pintype "input"))
      (node (ref "C19") (pin "1") (pinfunction "1_1") (pintype "input"))
      (node (ref "C2") (pin "1") (pinfunction "1_1") (pintype "input"))
      (node (ref "C21") (pin "2") (pinfunction "2_2") (pintype "input"))
      (node (ref "C22") (pin "2") (pinfunction "2_2") (pintype "input"))
      (node (ref "C24") (pin "1") (pinfunction "1_1") (pintype "input"))
      (node (ref "C25") (pin "1") (pinfunction "1_1") (pintype "input"))
      (node (ref "C26") (pin "1") (pinfunction "1_1") (pintype "input"))
      (node (ref "C27") (pin "2") (pinfunction "2_2") (pintype "input"))
      (node (ref "C29") (pin "1") (pinfunction "1_1") (pintype "input"))
      (node (ref "C30") (pin "1") (pinfunction "1_1") (pintype "input"))
      (node (ref "C31") (pin "1") (pinfunction "1_1") (pintype "input"))
      (node (ref "C32") (pin "1") (pinfunction "1_1") (pintype "input"))
      (node (ref "C35") (pin "1") (pinfunction "1_1") (pintype "input"))
      (node (ref "C36") (pin "1") (pinfunction "1_1") (pintype "input"))
      (node (ref "C37") (pin "1") (pinfunction "1_1") (pintype "input"))
      (node (ref "C38") (pin "1") (pinfunction "1_1") (pintype "input"))
      (node (ref "C39") (pin "1") (pinfunction "1_1") (pintype "input"))
      (node (ref "C4") (pin "2") (pinfunction "2_2") (pintype "input"))
      (node (ref "C40") (pin "1") (pinfunction "1_1") (pintype "input"))
      (node (ref "C41") (pin "1") (pinfunction "1_1") (pintype "input"))
      (node (ref "C44") (pin "1") (pinfunction "1_1") (pintype "input"))
      (node (ref "C45") (pin "1") (pinfunction "1_1") (pintype "input"))
      (node (ref "C46") (pin "1") (pinfunction "1_1") (pintype "input"))
      (node (ref "C47") (pin "1") (pinfunction "1_1") (pintype "input"))
      (node (ref "C48") (pin "1") (pinfunction "1_1") (pintype "input"))
      (node (ref "C49") (pin "1") (pinfunction "1_1") (pintype "input"))
      (node (ref "C5") (pin "2") (pinfunction "2_2") (pintype "input"))
      (node (ref "C57") (pin "1") (pinfunction "1_1") (pintype "input"))
      (node (ref "C6") (pin "1") (pinfunction "1_1") (pintype "input"))
      (node (ref "C62") (pin "1") (pinfunction "1_1") (pintype "input"))
      (node (ref "C63") (pin "1") (pinfunction "1_1") (pintype "input"))
      (node (ref "C66") (pin "1") (pinfunction "1_1") (pintype "input"))
      (node (ref "C67") (pin "1") (pinfunction "1_1") (pintype "input"))
      (node (ref "C7") (pin "1") (pinfunction "1_1") (pintype "input"))
      (node (ref "C70") (pin "1") (pinfunction "1_1") (pintype "input"))
      (node (ref "C71") (pin "2") (pinfunction "2_2") (pintype "input"))
      (node (ref "C74") (pin "1") (pinfunction "1_1") (pintype "input"))
      (node (ref "C75") (pin "1") (pinfunction "1_1") (pintype "input"))
      (node (ref "C79") (pin "2") (pinfunction "2_2") (pintype "input"))
      (node (ref "C8") (pin "2") (pinfunction "2_2") (pintype "input"))
      (node (ref "C82") (pin "1") (pinfunction "1_1") (pintype "input"))
      (node (ref "C83") (pin "1") (pinfunction "1_1") (pintype "input"))
      (node (ref "C86") (pin "2") (pinfunction "2_2") (pintype "input"))
      (node (ref "C89") (pin "1") (pinfunction "1_1") (pintype "input"))
      (node (ref "C9") (pin "1") (pinfunction "1_1") (pintype "input"))
      (node (ref "C92") (pin "2") (pinfunction "2_2") (pintype "input"))
      (node (ref "C93") (pin "2") (pinfunction "2_2") (pintype "input"))
      (node (ref "CAN2") (pin "3") (pinfunction "3_3") (pintype "input"))
      (node (ref "CAN2") (pin "4") (pinfunction "4_4") (pintype "input"))
      (node (ref "Cap") (pin "2") (pinfunction "2_2") (pintype "input"))
      (node (ref "Chassis") (pin "2") (pinfunction "2_2") (pintype "input"))
      (node (ref "D1") (pin "2") (pinfunction "GND_2") (pintype "unspecified"))
      (node (ref "D16") (pin "1") (pinfunction "A_1") (pintype "unspecified"))
      (node (ref "D2") (pin "2") (pinfunction "GND_2") (pintype "unspecified"))
      (node (ref "D20") (pin "1") (pinfunction "A_1") (pintype "unspecified"))
      (node (ref "D3") (pin "1") (pinfunction "1_1") (pintype "input"))
      (node (ref "D8") (pin "1") (pinfunction "K_1") (pintype "unspecified"))
      (node (ref "GH1") (pin "1") (pinfunction "1_1") (pintype "input"))
      (node (ref "GH1") (pin "5") (pinfunction "5_5") (pintype "input"))
      (node (ref "GH1") (pin "6") (pinfunction "6_6") (pintype "input"))
      (node (ref "GH2") (pin "1") (pinfunction "1_1") (pintype "input"))
      (node (ref "GH2") (pin "5") (pinfunction "5_5") (pintype "input"))
      (node (ref "GH2") (pin "6") (pinfunction "6_6") (pintype "input"))
      (node (ref "Q1") (pin "2") (pinfunction "E_2") (pintype "input"))
      (node (ref "Q3") (pin "1") (pinfunction "S_1") (pintype "unspecified"))
      (node (ref "Q3") (pin "2") (pinfunction "S_2") (pintype "unspecified"))
      (node (ref "Q3") (pin "3") (pinfunction "S_3") (pintype "unspecified"))
      (node (ref "Q5") (pin "1") (pinfunction "S_1") (pintype "unspecified"))
      (node (ref "Q5") (pin "2") (pinfunction "S_2") (pintype "unspecified"))
      (node (ref "Q5") (pin "3") (pinfunction "S_3") (pintype "unspecified"))
      (node (ref "R16") (pin "1") (pinfunction "1_1") (pintype "input"))
      (node (ref "R21") (pin "2") (pinfunction "2_2") (pintype "input"))
      (node (ref "R22") (pin "2") (pinfunction "2_2") (pintype "input"))
      (node (ref "R24") (pin "1") (pinfunction "1_1") (pintype "input"))
      (node (ref "R28") (pin "2") (pinfunction "2_2") (pintype "input"))
      (node (ref "R29") (pin "2") (pinfunction "2_2") (pintype "input"))
      (node (ref "R31") (pin "1") (pinfunction "1_1") (pintype "input"))
      (node (ref "R35") (pin "1") (pinfunction "1_1") (pintype "input"))
      (node (ref "R36") (pin "1") (pinfunction "1_1") (pintype "input"))
      (node (ref "R37") (pin "1") (pinfunction "1_1") (pintype "input"))
      (node (ref "R43") (pin "1") (pinfunction "1_1") (pintype "input"))
      (node (ref "R44") (pin "1") (pinfunction "1_1") (pintype "input"))
      (node (ref "R45") (pin "1") (pinfunction "1_1") (pintype "input"))
      (node (ref "R49") (pin "1") (pinfunction "1_1") (pintype "input"))
      (node (ref "R53") (pin "1") (pinfunction "1_1") (pintype "input"))
      (node (ref "R56") (pin "1") (pinfunction "1_1") (pintype "input"))
      (node (ref "R6") (pin "1") (pinfunction "1_1") (pintype "input"))
      (node (ref "R60") (pin "1") (pinfunction "1_1") (pintype "input"))
      (node (ref "R66") (pin "1") (pinfunction "1_1") (pintype "input"))
      (node (ref "SWD1") (pin "1") (pinfunction "1_1") (pintype "input"))
      (node (ref "SWD1") (pin "5") (pinfunction "5_5") (pintype "input"))
      (node (ref "SWD1") (pin "6") (pinfunction "6_6") (pintype "input"))
      (node (ref "U1") (pin "15") (pinfunction "VSS_15") (pintype "input"))
      (node (ref "U1") (pin "27") (pinfunction "VSSA_27") (pintype "input"))
      (node (ref "U1") (pin "31") (pinfunction "VSS_31") (pintype "input"))
      (node (ref "U1") (pin "47") (pinfunction "VSS_47") (pintype "input"))
      (node (ref "U1") (pin "63") (pinfunction "VSS_63") (pintype "input"))
      (node (ref "U10") (pin "7") (pinfunction "VSS_7") (pintype "unspecified"))
      (node (ref "U11") (pin "2") (pinfunction "A_2") (pintype "unspecified"))
      (node (ref "U13") (pin "7") (pinfunction "GND_7") (pintype "unspecified"))
      (node (ref "U13") (pin "9") (pinfunction "EP_9") (pintype "unspecified"))
      (node (ref "U14") (pin "2") (pinfunction "2_2") (pintype "input"))
      (node (ref "U16") (pin "1") (pinfunction "ADJ/GND_1") (pintype "input"))
      (node (ref "U17") (pin "2") (pinfunction "2_2") (pintype "input"))
      (node (ref "U18") (pin "2") (pinfunction "A_2") (pintype "unspecified"))
      (node (ref "U19") (pin "2") (pinfunction "A_2") (pintype "unspecified"))
      (node (ref "U2") (pin "2") (pinfunction "GND_2") (pintype "input"))
      (node (ref "U2") (pin "4") (pinfunction "GND_4") (pintype "input"))
      (node (ref "U21") (pin "7") (pinfunction "GND_7") (pintype "unspecified"))
      (node (ref "U21") (pin "9") (pinfunction "EP_9") (pintype "unspecified"))
      (node (ref "U22") (pin "2") (pinfunction "2_2") (pintype "input"))
      (node (ref "U27") (pin "1") (pinfunction "NC_1") (pintype "input"))
      (node (ref "U29") (pin "1") (pinfunction "NC_1") (pintype "input"))
      (node (ref "U3") (pin "2") (pinfunction "GND_2") (pintype "input"))
      (node (ref "U3") (pin "8") (pinfunction "S_8") (pintype "input"))
      (node (ref "U31") (pin "4") (pinfunction "V-_4") (pintype "unspecified"))
      (node (ref "U4") (pin "1") (pinfunction "1_1") (pintype "input"))
      (node (ref "U7") (pin "7") (pinfunction "VSS_7") (pintype "unspecified"))
      (node (ref "U8") (pin "2") (pinfunction "A_2") (pintype "unspecified"))
    )
    (net (code "19") (name "LED1") (class "Default")
      (node (ref "R13") (pin "2") (pinfunction "2_2") (pintype "input"))
      (node (ref "U1") (pin "8") (pinfunction "PC0_8") (pintype "input"))
    )
    (net (code "20") (name "LED2") (class "Default")
      (node (ref "R15") (pin "2") (pinfunction "2_2") (pintype "input"))
      (node (ref "U1") (pin "9") (pinfunction "PC1_9") (pintype "input"))
    )
    (net (code "21") (name "LED3") (class "Default")
      (node (ref "R17") (pin "2") (pinfunction "2_2") (pintype "input"))
      (node (ref "U1") (pin "10") (pinfunction "PC2_10") (pintype "input"))
    )
    (net (code "22") (name "Net-(BUZZER1--)") (class "Default")
      (node (ref "BUZZER1") (pin "2") (pinfunction "-_2") (pintype "input"))
      (node (ref "Q1") (pin "3") (pinfunction "C_3") (pintype "input"))
    )
    (net (code "23") (name "Net-(C35-Pad2)") (class "Default")
      (node (ref "C35") (pin "2") (pinfunction "2_2") (pintype "input"))
      (node (ref "C36") (pin "2") (pinfunction "2_2") (pintype "input"))
      (node (ref "C37") (pin "2") (pinfunction "2_2") (pintype "input"))
      (node (ref "C38") (pin "2") (pinfunction "2_2") (pintype "input"))
      (node (ref "C39") (pin "2") (pinfunction "2_2") (pintype "input"))
      (node (ref "L2") (pin "2") (pinfunction "2_2") (pintype "unspecified"))
      (node (ref "R32") (pin "2") (pinfunction "2_2") (pintype "input"))
      (node (ref "U12") (pin "1") (pinfunction "1_1") (pintype "unspecified"))
      (node (ref "U14") (pin "1") (pinfunction "1_1") (pintype "input"))
    )
    (net (code "24") (name "Net-(C45-Pad2)") (class "Default")
      (node (ref "C45") (pin "2") (pinfunction "2_2") (pintype "input"))
      (node (ref "R34") (pin "1") (pinfunction "1_1") (pintype "input"))
    )
    (net (code "25") (name "Net-(C57-Pad2)") (class "Default")
      (node (ref "C57") (pin "2") (pinfunction "2_2") (pintype "input"))
      (node (ref "F1") (pin "1") (pinfunction "1_1") (pintype "unspecified"))
      (node (ref "L4") (pin "2") (pinfunction "2_2") (pintype "unspecified"))
      (node (ref "R40") (pin "2") (pinfunction "2_2") (pintype "input"))
      (node (ref "U22") (pin "1") (pinfunction "1_1") (pintype "input"))
    )
    (net (code "26") (name "Net-(C67-Pad2)") (class "Default")
      (node (ref "C67") (pin "2") (pinfunction "2_2") (pintype "input"))
      (node (ref "R42") (pin "1") (pinfunction "1_1") (pintype "input"))
    )
    (net (code "27") (name "Net-(D7-A)") (class "Default")
      (node (ref "D7") (pin "2") (pinfunction "A_2") (pintype "unspecified"))
      (node (ref "Q2") (pin "4") (pinfunction "G_4") (pintype "unspecified"))
      (node (ref "R19") (pin "1") (pinfunction "1_1") (pintype "input"))
      (node (ref "R20") (pin "2") (pinfunction "2_2") (pintype "input"))
    )
    (net (code "28") (name "Net-(D7-K)") (class "Default")
      (node (ref "D7") (pin "1") (pinfunction "K_1") (pintype "unspecified"))
      (node (ref "R20") (pin "1") (pinfunction "1_1") (pintype "input"))
      (node (ref "U7") (pin "3") (pinfunction "HO_3") (pintype "unspecified"))
    )
    (net (code "29") (name "Net-(D10-A)") (class "Default")
      (node (ref "D10") (pin "2") (pinfunction "A_2") (pintype "unspecified"))
      (node (ref "Q3") (pin "4") (pinfunction "G_4") (pintype "unspecified"))
      (node (ref "R23") (pin "2") (pinfunction "2_2") (pintype "input"))
      (node (ref "R24") (pin "2") (pinfunction "2_2") (pintype "input"))
    )
    (net (code "30") (name "Net-(D10-K)") (class "Default")
      (node (ref "D10") (pin "1") (pinfunction "K_1") (pintype "unspecified"))
      (node (ref "R23") (pin "1") (pinfunction "1_1") (pintype "input"))
      (node (ref "U7") (pin "8") (pinfunction "LO_8") (pintype "unspecified"))
    )
    (net (code "31") (name "Net-(D13-A)") (class "Default")
      (node (ref "D13") (pin "2") (pinfunction "A_2") (pintype "unspecified"))
      (node (ref "Q4") (pin "4") (pinfunction "G_4") (pintype "unspecified"))
      (node (ref "R26") (pin "1") (pinfunction "1_1") (pintype "input"))
      (node (ref "R27") (pin "2") (pinfunction "2_2") (pintype "input"))
    )
    (net (code "32") (name "Net-(D13-K)") (class "Default")
      (node (ref "D13") (pin "1") (pinfunction "K_1") (pintype "unspecified"))
      (node (ref "R27") (pin "1") (pinfunction "1_1") (pintype "input"))
      (node (ref "U10") (pin "3") (pinfunction "HO_3") (pintype "unspecified"))
    )
    (net (code "33") (name "Net-(D15-A)") (class "Default")
      (node (ref "D15") (pin "2") (pinfunction "A_2") (pintype "unspecified"))
      (node (ref "Q5") (pin "4") (pinfunction "G_4") (pintype "unspecified"))
      (node (ref "R30") (pin "2") (pinfunction "2_2") (pintype "input"))
      (node (ref "R31") (pin "2") (pinfunction "2_2") (pintype "input"))
    )
    (net (code "34") (name "Net-(D15-K)") (class "Default")
      (node (ref "D15") (pin "1") (pinfunction "K_1") (pintype "unspecified"))
      (node (ref "R30") (pin "1") (pinfunction "1_1") (pintype "input"))
      (node (ref "U10") (pin "8") (pinfunction "LO_8") (pintype "unspecified"))
    )
    (net (code "35") (name "Net-(D16-K)") (class "Default")
      (node (ref "C34") (pin "2") (pinfunction "2_2") (pintype "input"))
      (node (ref "D16") (pin "2") (pinfunction "K_2") (pintype "unspecified"))
      (node (ref "L2") (pin "1") (pinfunction "1_1") (pintype "unspecified"))
      (node (ref "U13") (pin "8") (pinfunction "SW_8") (pintype "unspecified"))
    )
    (net (code "36") (name "Net-(D20-K)") (class "Default")
      (node (ref "C56") (pin "2") (pinfunction "2_2") (pintype "input"))
      (node (ref "D20") (pin "2") (pinfunction "K_2") (pintype "unspecified"))
      (node (ref "L4") (pin "1") (pinfunction "1_1") (pintype "unspecified"))
      (node (ref "U21") (pin "8") (pinfunction "SW_8") (pintype "unspecified"))
    )
    (net (code "37") (name "Net-(D21-A)") (class "Default")
      (node (ref "C33") (pin "1") (pinfunction "1_1") (pintype "input"))
      (node (ref "D21") (pin "2") (pinfunction "A_2") (pintype "unspecified"))
      (node (ref "Q4") (pin "1") (pinfunction "S_1") (pintype "unspecified"))
      (node (ref "Q4") (pin "2") (pinfunction "S_2") (pintype "unspecified"))
      (node (ref "Q4") (pin "3") (pinfunction "S_3") (pintype "unspecified"))
      (node (ref "Q5") (pin "5") (pinfunction "D_5") (pintype "unspecified"))
      (node (ref "Q5") (pin "6") (pinfunction "D_6") (pintype "unspecified"))
      (node (ref "Q5") (pin "7") (pinfunction "D_7") (pintype "unspecified"))
      (node (ref "Q5") (pin "8") (pinfunction "D_8") (pintype "unspecified"))
      (node (ref "R26") (pin "2") (pinfunction "2_2") (pintype "input"))
      (node (ref "U10") (pin "4") (pinfunction "HS_4") (pintype "unspecified"))
      (node (ref "U11") (pin "1") (pinfunction "C_1") (pintype "unspecified"))
      (node (ref "U6") (pin "1") (pinfunction "1_1") (pintype "unspecified"))
      (node (ref "U9") (pin "2") (pinfunction "A_2") (pintype "unspecified"))
    )
    (net (code "38") (name "Net-(FB1-Pad2)") (class "Default")
      (node (ref "FB1") (pin "2") (pinfunction "2_2") (pintype "input"))
      (node (ref "U12") (pin "2") (pinfunction "2_2") (pintype "unspecified"))
    )
    (net (code "39") (name "Net-(GH1-Pad3)") (class "Default")
      (node (ref "GH1") (pin "3") (pinfunction "3_3") (pintype "input"))
      (node (ref "R1") (pin "1") (pinfunction "1_1") (pintype "input"))
    )
    (net (code "40") (name "Net-(GH2-Pad3)") (class "Default")
      (node (ref "GH2") (pin "3") (pinfunction "3_3") (pintype "input"))
      (node (ref "R9") (pin "1") (pinfunction "1_1") (pintype "input"))
    )
    (net (code "41") (name "Net-(LED1-C)") (class "Default")
      (node (ref "LED1") (pin "2") (pinfunction "C_2") (pintype "input"))
      (node (ref "R13") (pin "1") (pinfunction "1_1") (pintype "input"))
    )
    (net (code "42") (name "Net-(LED2-C)") (class "Default")
      (node (ref "LED2") (pin "2") (pinfunction "C_2") (pintype "input"))
      (node (ref "R15") (pin "1") (pinfunction "1_1") (pintype "input"))
    )
    (net (code "43") (name "Net-(LED3-C)") (class "Default")
      (node (ref "LED3") (pin "2") (pinfunction "C_2") (pintype "input"))
      (node (ref "R17") (pin "1") (pinfunction "1_1") (pintype "input"))
    )
    (net (code "44") (name "Net-(Q1-B)") (class "Default")
      (node (ref "Q1") (pin "1") (pinfunction "B_1") (pintype "input"))
      (node (ref "R14") (pin "2") (pinfunction "2_2") (pintype "input"))
      (node (ref "R16") (pin "2") (pinfunction "2_2") (pintype "input"))
    )
    (net (code "45") (name "Net-(R3-Pad1)") (class "Default")
      (node (ref "R3") (pin "1") (pinfunction "1_1") (pintype "input"))
      (node (ref "SWD1") (pin "3") (pinfunction "3_3") (pintype "input"))
    )
    (net (code "46") (name "Net-(R4-Pad1)") (class "Default")
      (node (ref "R4") (pin "1") (pinfunction "1_1") (pintype "input"))
      (node (ref "SWD1") (pin "2") (pinfunction "2_2") (pintype "input"))
    )
    (net (code "47") (name "Net-(U3-CANH)") (class "Default")
      (node (ref "CAN2") (pin "1") (pinfunction "1_1") (pintype "input"))
      (node (ref "R10") (pin "1") (pinfunction "1_1") (pintype "input"))
      (node (ref "U3") (pin "7") (pinfunction "CANH_7") (pintype "input"))
    )
    (net (code "48") (name "Net-(U3-CANL)") (class "Default")
      (node (ref "CAN2") (pin "2") (pinfunction "2_2") (pintype "input"))
      (node (ref "R10") (pin "2") (pinfunction "2_2") (pintype "input"))
      (node (ref "U3") (pin "6") (pinfunction "CANL_6") (pintype "input"))
    )
    (net (code "49") (name "Net-(U3-RXD)") (class "Default")
      (node (ref "R8") (pin "1") (pinfunction "1_1") (pintype "input"))
      (node (ref "U3") (pin "4") (pinfunction "RXD_4") (pintype "input"))
    )
    (net (code "50") (name "Net-(U3-n.c.)") (class "Default")
      (node (ref "C8") (pin "1") (pinfunction "1_1") (pintype "input"))
      (node (ref "U3") (pin "5") (pinfunction "n.c._5") (pintype "input"))
    )
    (net (code "51") (name "Net-(U5-A)") (class "Default")
      (node (ref "C20") (pin "1") (pinfunction "1_1") (pintype "input"))
      (node (ref "Q2") (pin "1") (pinfunction "S_1") (pintype "unspecified"))
      (node (ref "Q2") (pin "2") (pinfunction "S_2") (pintype "unspecified"))
      (node (ref "Q2") (pin "3") (pinfunction "S_3") (pintype "unspecified"))
      (node (ref "Q3") (pin "5") (pinfunction "D_5") (pintype "unspecified"))
      (node (ref "Q3") (pin "6") (pinfunction "D_6") (pintype "unspecified"))
      (node (ref "Q3") (pin "7") (pinfunction "D_7") (pintype "unspecified"))
      (node (ref "Q3") (pin "8") (pinfunction "D_8") (pintype "unspecified"))
      (node (ref "R19") (pin "2") (pinfunction "2_2") (pintype "input"))
      (node (ref "U5") (pin "2") (pinfunction "A_2") (pintype "unspecified"))
      (node (ref "U6") (pin "2") (pinfunction "2_2") (pintype "unspecified"))
      (node (ref "U7") (pin "4") (pinfunction "HS_4") (pintype "unspecified"))
      (node (ref "U8") (pin "1") (pinfunction "C_1") (pintype "unspecified"))
    )
    (net (code "52") (name "Net-(U7-HB)") (class "Default")
      (node (ref "C20") (pin "2") (pinfunction "2_2") (pintype "input"))
      (node (ref "U7") (pin "2") (pinfunction "HB_2") (pintype "unspecified"))
    )
    (net (code "53") (name "Net-(U10-HB)") (class "Default")
      (node (ref "C33") (pin "2") (pinfunction "2_2") (pintype "input"))
      (node (ref "U10") (pin "2") (pinfunction "HB_2") (pintype "unspecified"))
    )
    (net (code "54") (name "Net-(U13-BOOT)") (class "Default")
      (node (ref "C34") (pin "1") (pinfunction "1_1") (pintype "input"))
      (node (ref "U13") (pin "1") (pinfunction "BOOT_1") (pintype "unspecified"))
    )
    (net (code "55") (name "Net-(U13-COMP)") (class "Default")
      (node (ref "C44") (pin "2") (pinfunction "2_2") (pintype "input"))
      (node (ref "R34") (pin "2") (pinfunction "2_2") (pintype "input"))
      (node (ref "U13") (pin "6") (pinfunction "COMP_6") (pintype "unspecified"))
    )
    (net (code "56") (name "Net-(U13-EN)") (class "Default")
      (node (ref "R33") (pin "1") (pinfunction "1_1") (pintype "input"))
      (node (ref "R37") (pin "2") (pinfunction "2_2") (pintype "input"))
      (node (ref "U13") (pin "3") (pinfunction "EN_3") (pintype "unspecified"))
    )
    (net (code "57") (name "Net-(U13-FB)") (class "Default")
      (node (ref "R32") (pin "1") (pinfunction "1_1") (pintype "input"))
      (node (ref "R36") (pin "2") (pinfunction "2_2") (pintype "input"))
      (node (ref "U13") (pin "5") (pinfunction "FB_5") (pintype "unspecified"))
    )
    (net (code "58") (name "Net-(U13-RT{slash}CLK)") (class "Default")
      (node (ref "R35") (pin "2") (pinfunction "2_2") (pintype "input"))
      (node (ref "U13") (pin "4") (pinfunction "RT/CLK_4") (pintype "unspecified"))
    )
    (net (code "59") (name "Net-(U21-BOOT)") (class "Default")
      (node (ref "C56") (pin "1") (pinfunction "1_1") (pintype "input"))
      (node (ref "U21") (pin "1") (pinfunction "BOOT_1") (pintype "unspecified"))
    )
    (net (code "60") (name "Net-(U21-COMP)") (class "Default")
      (node (ref "C66") (pin "2") (pinfunction "2_2") (pintype "input"))
      (node (ref "R42") (pin "2") (pinfunction "2_2") (pintype "input"))
      (node (ref "U21") (pin "6") (pinfunction "COMP_6") (pintype "unspecified"))
    )
    (net (code "61") (name "Net-(U21-EN)") (class "Default")
      (node (ref "R41") (pin "1") (pinfunction "1_1") (pintype "input"))
      (node (ref "R45") (pin "2") (pinfunction "2_2") (pintype "input"))
      (node (ref "U21") (pin "3") (pinfunction "EN_3") (pintype "unspecified"))
    )
    (net (code "62") (name "Net-(U21-FB)") (class "Default")
      (node (ref "R40") (pin "1") (pinfunction "1_1") (pintype "input"))
      (node (ref "R44") (pin "2") (pinfunction "2_2") (pintype "input"))
      (node (ref "U21") (pin "5") (pinfunction "FB_5") (pintype "unspecified"))
    )
    (net (code "63") (name "Net-(U21-RT{slash}CLK)") (class "Default")
      (node (ref "R43") (pin "2") (pinfunction "2_2") (pintype "input"))
      (node (ref "U21") (pin "4") (pinfunction "RT/CLK_4") (pintype "unspecified"))
    )
    (net (code "64") (name "Net-(U25-IN+)") (class "Default")
      (node (ref "C71") (pin "1") (pinfunction "1_1") (pintype "input"))
      (node (ref "C73") (pin "2") (pinfunction "2_2") (pintype "input"))
      (node (ref "R48") (pin "2") (pinfunction "2_2") (pintype "input"))
      (node (ref "U25") (pin "2") (pinfunction "IN+_2") (pintype "input"))
    )
    (net (code "65") (name "Net-(U25-IN-)") (class "Default")
      (node (ref "C73") (pin "1") (pinfunction "1_1") (pintype "input"))
      (node (ref "C75") (pin "2") (pinfunction "2_2") (pintype "input"))
      (node (ref "R51") (pin "2") (pinfunction "2_2") (pintype "input"))
      (node (ref "U25") (pin "3") (pinfunction "IN-_3") (pintype "input"))
    )
    (net (code "66") (name "Net-(U25-OUT)") (class "Default")
      (node (ref "R46") (pin "1") (pinfunction "1_1") (pintype "input"))
      (node (ref "U25") (pin "8") (pinfunction "OUT_8") (pintype "input"))
    )
    (net (code "67") (name "Net-(U27-IN+)") (class "Default")
      (node (ref "C79") (pin "1") (pinfunction "1_1") (pintype "input"))
      (node (ref "C81") (pin "2") (pinfunction "2_2") (pintype "input"))
      (node (ref "R58") (pin "2") (pinfunction "2_2") (pintype "input"))
      (node (ref "U27") (pin "2") (pinfunction "IN+_2") (pintype "input"))
    )
    (net (code "68") (name "Net-(U27-IN-)") (class "Default")
      (node (ref "C81") (pin "1") (pinfunction "1_1") (pintype "input"))
      (node (ref "C83") (pin "2") (pinfunction "2_2") (pintype "input"))
      (node (ref "R61") (pin "2") (pinfunction "2_2") (pintype "input"))
      (node (ref "U27") (pin "3") (pinfunction "IN-_3") (pintype "input"))
    )
    (net (code "69") (name "Net-(U27-OUT)") (class "Default")
      (node (ref "R54") (pin "1") (pinfunction "1_1") (pintype "input"))
      (node (ref "U27") (pin "8") (pinfunction "OUT_8") (pintype "input"))
    )
    (net (code "70") (name "Net-(U29-IN+)") (class "Default")
      (node (ref "C86") (pin "1") (pinfunction "1_1") (pintype "input"))
      (node (ref "C88") (pin "2") (pinfunction "2_2") (pintype "input"))
      (node (ref "R63") (pin "2") (pinfunction "2_2") (pintype "input"))
      (node (ref "U29") (pin "2") (pinfunction "IN+_2") (pintype "input"))
    )
    (net (code "71") (name "Net-(U29-IN-)") (class "Default")
      (node (ref "C88") (pin "1") (pinfunction "1_1") (pintype "input"))
      (node (ref "C89") (pin "2") (pinfunction "2_2") (pintype "input"))
      (node (ref "R65") (pin "2") (pinfunction "2_2") (pintype "input"))
      (node (ref "U29") (pin "3") (pinfunction "IN-_3") (pintype "input"))
    )
    (net (code "72") (name "Net-(U29-OUT)") (class "Default")
      (node (ref "R62") (pin "1") (pinfunction "1_1") (pintype "input"))
      (node (ref "U29") (pin "8") (pinfunction "OUT_8") (pintype "input"))
    )
    (net (code "73") (name "Net-(U31A-IN_B+)") (class "Default")
      (node (ref "R52") (pin "2") (pinfunction "2_2") (pintype "input"))
      (node (ref "R53") (pin "2") (pinfunction "2_2") (pintype "input"))
      (node (ref "U31") (pin "5") (pinfunction "IN_B+_5") (pintype "unspecified"))
    )
    (net (code "74") (name "Net-(U31A-IN_B-)") (class "Default")
      (node (ref "R47") (pin "1") (pinfunction "1_1") (pintype "input"))
      (node (ref "R49") (pin "2") (pinfunction "2_2") (pintype "input"))
      (node (ref "U31") (pin "6") (pinfunction "IN_B-_6") (pintype "unspecified"))
    )
    (net (code "75") (name "Net-(U31A-VOUT_B)") (class "Default")
      (node (ref "R47") (pin "2") (pinfunction "2_2") (pintype "input"))
      (node (ref "R50") (pin "1") (pinfunction "1_1") (pintype "input"))
      (node (ref "U31") (pin "7") (pinfunction "VOUT_B_7") (pintype "output"))
    )
    (net (code "76") (name "Net-(U31B-IN_A+)") (class "Default")
      (node (ref "R59") (pin "2") (pinfunction "2_2") (pintype "input"))
      (node (ref "R60") (pin "2") (pinfunction "2_2") (pintype "input"))
      (node (ref "U31") (pin "3") (pinfunction "IN_A+_3") (pintype "unspecified"))
    )
    (net (code "77") (name "Net-(U31B-IN_A-)") (class "Default")
      (node (ref "R55") (pin "1") (pinfunction "1_1") (pintype "input"))
      (node (ref "R56") (pin "2") (pinfunction "2_2") (pintype "input"))
      (node (ref "U31") (pin "2") (pinfunction "IN_A-_2") (pintype "unspecified"))
    )
    (net (code "78") (name "Net-(U31B-VOUT_A)") (class "Default")
      (node (ref "R55") (pin "2") (pinfunction "2_2") (pintype "input"))
      (node (ref "R57") (pin "1") (pinfunction "1_1") (pintype "input"))
      (node (ref "U31") (pin "1") (pinfunction "VOUT_A_1") (pintype "output"))
    )
    (net (code "79") (name "OPAMP1_VINP") (class "Default")
      (node (ref "C78") (pin "1") (pinfunction "1_1") (pintype "input"))
      (node (ref "R54") (pin "2") (pinfunction "2_2") (pintype "input"))
      (node (ref "U1") (pin "17") (pinfunction "PA3_17") (pintype "input"))
    )
    (net (code "80") (name "OPAMP2_VINP") (class "Default")
      (node (ref "C69") (pin "1") (pinfunction "1_1") (pintype "input"))
      (node (ref "R46") (pin "2") (pinfunction "2_2") (pintype "input"))
      (node (ref "U1") (pin "21") (pinfunction "PA7_21") (pintype "input"))
    )
    (net (code "81") (name "OPAMP4_VINP") (class "Default")
      (node (ref "C85") (pin "1") (pinfunction "1_1") (pintype "input"))
      (node (ref "R62") (pin "2") (pinfunction "2_2") (pintype "input"))
      (node (ref "U1") (pin "33") (pinfunction "PB11_33") (pintype "input"))
    )
    (net (code "82") (name "OSC_IN") (class "Default")
      (node (ref "C4") (pin "1") (pinfunction "1_1") (pintype "input"))
      (node (ref "R5") (pin "1") (pinfunction "1_1") (pintype "input"))
      (node (ref "U1") (pin "5") (pinfunction "PF0-OSC_IN_5") (pintype "input"))
      (node (ref "U2") (pin "1") (pinfunction "OSC1_1") (pintype "input"))
    )
    (net (code "83") (name "OSC_OUT") (class "Default")
      (node (ref "C5") (pin "1") (pinfunction "1_1") (pintype "input"))
      (node (ref "R5") (pin "2") (pinfunction "2_2") (pintype "input"))
      (node (ref "U1") (pin "6") (pinfunction "PF1-OSC_OUT_6") (pintype "input"))
      (node (ref "U2") (pin "3") (pinfunction "OSC2_3") (pintype "input"))
    )
    (net (code "84") (name "RESET") (class "Default")
      (node (ref "C13") (pin "2") (pinfunction "2_2") (pintype "input"))
      (node (ref "R7") (pin "1") (pinfunction "1_1") (pintype "input"))
      (node (ref "U1") (pin "7") (pinfunction "PG10-NRST_7") (pintype "input"))
      (node (ref "U4") (pin "2") (pinfunction "2_2") (pintype "input"))
    )
    (net (code "85") (name "Timer_A1") (class "Default")
      (node (ref "R21") (pin "1") (pinfunction "1_1") (pintype "input"))
      (node (ref "U1") (pin "42") (pinfunction "PA8_42") (pintype "input"))
      (node (ref "U7") (pin "5") (pinfunction "HI_5") (pintype "unspecified"))
    )
    (net (code "86") (name "Timer_A2") (class "Default")
      (node (ref "R22") (pin "1") (pinfunction "1_1") (pintype "input"))
      (node (ref "U1") (pin "43") (pinfunction "PA9_43") (pintype "input"))
      (node (ref "U7") (pin "6") (pinfunction "LI_6") (pintype "unspecified"))
    )
    (net (code "87") (name "Timer_B1") (class "Default")
      (node (ref "R29") (pin "1") (pinfunction "1_1") (pintype "input"))
      (node (ref "U1") (pin "44") (pinfunction "PA10_44") (pintype "input"))
      (node (ref "U10") (pin "6") (pinfunction "LI_6") (pintype "unspecified"))
    )
    (net (code "88") (name "Timer_B2") (class "Default")
      (node (ref "R28") (pin "1") (pinfunction "1_1") (pintype "input"))
      (node (ref "U1") (pin "45") (pinfunction "PA11_45") (pintype "input"))
      (node (ref "U10") (pin "5") (pinfunction "HI_5") (pintype "unspecified"))
    )
    (net (code "89") (name "U1_RX") (class "Default")
      (node (ref "D1") (pin "1") (pinfunction "I/O_1") (pintype "unspecified"))
      (node (ref "R1") (pin "2") (pinfunction "2_2") (pintype "input"))
      (node (ref "U1") (pin "60") (pinfunction "PB7_60") (pintype "input"))
    )
    (net (code "90") (name "U1_TX") (class "Default")
      (node (ref "D1") (pin "6") (pinfunction "I/O_6") (pintype "unspecified"))
      (node (ref "GH1") (pin "2") (pinfunction "2_2") (pintype "input"))
      (node (ref "U1") (pin "59") (pinfunction "PB6_59") (pintype "input"))
    )
    (net (code "91") (name "U3_RX") (class "Default")
      (node (ref "D2") (pin "6") (pinfunction "I/O_6") (pintype "unspecified"))
      (node (ref "R9") (pin "2") (pinfunction "2_2") (pintype "input"))
      (node (ref "U1") (pin "53") (pinfunction "PC11_53") (pintype "input"))
    )
    (net (code "92") (name "U3_TX") (class "Default")
      (node (ref "D2") (pin "1") (pinfunction "I/O_1") (pintype "unspecified"))
      (node (ref "GH2") (pin "2") (pinfunction "2_2") (pintype "input"))
      (node (ref "U1") (pin "52") (pinfunction "PC10_52") (pintype "input"))
    )
    (net (code "93") (name "VREF3.3") (class "Default")
      (node (ref "C10") (pin "1") (pinfunction "1_1") (pintype "input"))
      (node (ref "C11") (pin "1") (pinfunction "1_1") (pintype "input"))
      (node (ref "C72") (pin "1") (pinfunction "1_1") (pintype "input"))
      (node (ref "C80") (pin "1") (pinfunction "1_1") (pintype "input"))
      (node (ref "C87") (pin "1") (pinfunction "1_1") (pintype "input"))
      (node (ref "U1") (pin "28") (pinfunction "VREF+_28") (pintype "input"))
      (node (ref "U24") (pin "2") (pinfunction "OUT_2") (pintype "unspecified"))
      (node (ref "U25") (pin "6") (pinfunction "REF2_6") (pintype "input"))
      (node (ref "U27") (pin "6") (pinfunction "REF2_6") (pintype "input"))
      (node (ref "U29") (pin "6") (pinfunction "REF2_6") (pintype "input"))
    )
    (net (code "94") (name "unconnected-(U1-PA0-Pad12)") (class "Default")
      (node (ref "U1") (pin "12") (pinfunction "PA0_12") (pintype "input"))
    )
    (net (code "95") (name "unconnected-(U1-PA1-Pad13)") (class "Default")
      (node (ref "U1") (pin "13") (pinfunction "PA1_13") (pintype "input"))
    )
    (net (code "96") (name "unconnected-(U1-PA4-Pad18)") (class "Default")
      (node (ref "U1") (pin "18") (pinfunction "PA4_18") (pintype "input"))
    )
    (net (code "97") (name "unconnected-(U1-PA5-Pad19)") (class "Default")
      (node (ref "U1") (pin "19") (pinfunction "PA5_19") (pintype "input"))
    )
    (net (code "98") (name "unconnected-(U1-PA6-Pad20)") (class "Default")
      (node (ref "U1") (pin "20") (pinfunction "PA6_20") (pintype "input"))
    )
    (net (code "99") (name "unconnected-(U1-PA12-Pad46)") (class "Default")
      (node (ref "U1") (pin "46") (pinfunction "PA12_46") (pintype "input"))
    )
    (net (code "100") (name "unconnected-(U1-PA15-Pad51)") (class "Default")
      (node (ref "U1") (pin "51") (pinfunction "PA15_51") (pintype "input"))
    )
    (net (code "101") (name "unconnected-(U1-PB2-Pad26)") (class "Default")
      (node (ref "U1") (pin "26") (pinfunction "PB2_26") (pintype "input"))
    )
    (net (code "102") (name "unconnected-(U1-PB3-Pad56)") (class "Default")
      (node (ref "U1") (pin "56") (pinfunction "PB3_56") (pintype "input"))
    )
    (net (code "103") (name "unconnected-(U1-PB4-Pad57)") (class "Default")
      (node (ref "U1") (pin "57") (pinfunction "PB4_57") (pintype "input"))
    )
    (net (code "104") (name "unconnected-(U1-PB5-Pad58)") (class "Default")
      (node (ref "U1") (pin "58") (pinfunction "PB5_58") (pintype "input"))
    )
    (net (code "105") (name "unconnected-(U1-PB10-Pad30)") (class "Default")
      (node (ref "U1") (pin "30") (pinfunction "PB10_30") (pintype "input"))
    )
    (net (code "106") (name "unconnected-(U1-PB13-Pad35)") (class "Default")
      (node (ref "U1") (pin "35") (pinfunction "PB13_35") (pintype "input"))
    )
    (net (code "107") (name "unconnected-(U1-PB15-Pad37)") (class "Default")
      (node (ref "U1") (pin "37") (pinfunction "PB15_37") (pintype "input"))
    )
    (net (code "108") (name "unconnected-(U1-PBO-Pad24)") (class "Default")
      (node (ref "U1") (pin "24") (pinfunction "PBO_24") (pintype "input"))
    )
    (net (code "109") (name "unconnected-(U1-PC3-Pad11)") (class "Default")
      (node (ref "U1") (pin "11") (pinfunction "PC3_11") (pintype "input"))
    )
    (net (code "110") (name "unconnected-(U1-PC4-Pad22)") (class "Default")
      (node (ref "U1") (pin "22") (pinfunction "PC4_22") (pintype "input"))
    )
    (net (code "111") (name "unconnected-(U1-PC5-Pad23)") (class "Default")
      (node (ref "U1") (pin "23") (pinfunction "PC5_23") (pintype "input"))
    )
    (net (code "112") (name "unconnected-(U1-PC6-Pad38)") (class "Default")
      (node (ref "U1") (pin "38") (pinfunction "PC6_38") (pintype "input"))
    )
    (net (code "113") (name "unconnected-(U1-PC7-Pad39)") (class "Default")
      (node (ref "U1") (pin "39") (pinfunction "PC7_39") (pintype "input"))
    )
    (net (code "114") (name "unconnected-(U1-PC8-Pad40)") (class "Default")
      (node (ref "U1") (pin "40") (pinfunction "PC8_40") (pintype "input"))
    )
    (net (code "115") (name "unconnected-(U1-PC9-Pad41)") (class "Default")
      (node (ref "U1") (pin "41") (pinfunction "PC9_41") (pintype "input"))
    )
    (net (code "116") (name "unconnected-(U1-PC12-Pad54)") (class "Default")
      (node (ref "U1") (pin "54") (pinfunction "PC12_54") (pintype "input"))
    )
    (net (code "117") (name "unconnected-(U1-PC13-Pad2)") (class "Default")
      (node (ref "U1") (pin "2") (pinfunction "PC13_2") (pintype "input"))
    )
    (net (code "118") (name "unconnected-(U1-PC14-OSC32_IN-Pad3)") (class "Default")
      (node (ref "U1") (pin "3") (pinfunction "PC14-OSC32_IN_3") (pintype "input"))
    )
    (net (code "119") (name "unconnected-(U1-PC15-OSC32_OUT-Pad4)") (class "Default")
      (node (ref "U1") (pin "4") (pinfunction "PC15-OSC32_OUT_4") (pintype "input"))
    )
    (net (code "120") (name "unconnected-(U1-PD2-Pad55)") (class "Default")
      (node (ref "U1") (pin "55") (pinfunction "PD2_55") (pintype "input"))
    )
    (net (code "121") (name "unconnected-(U25-NC-Pad1)") (class "Default")
      (node (ref "U25") (pin "1") (pinfunction "NC_1") (pintype "input"))
    )
  )
)
